# SCH_OpenIDS2.net
KiCad netlist of a schematic drawn in EasyEDA
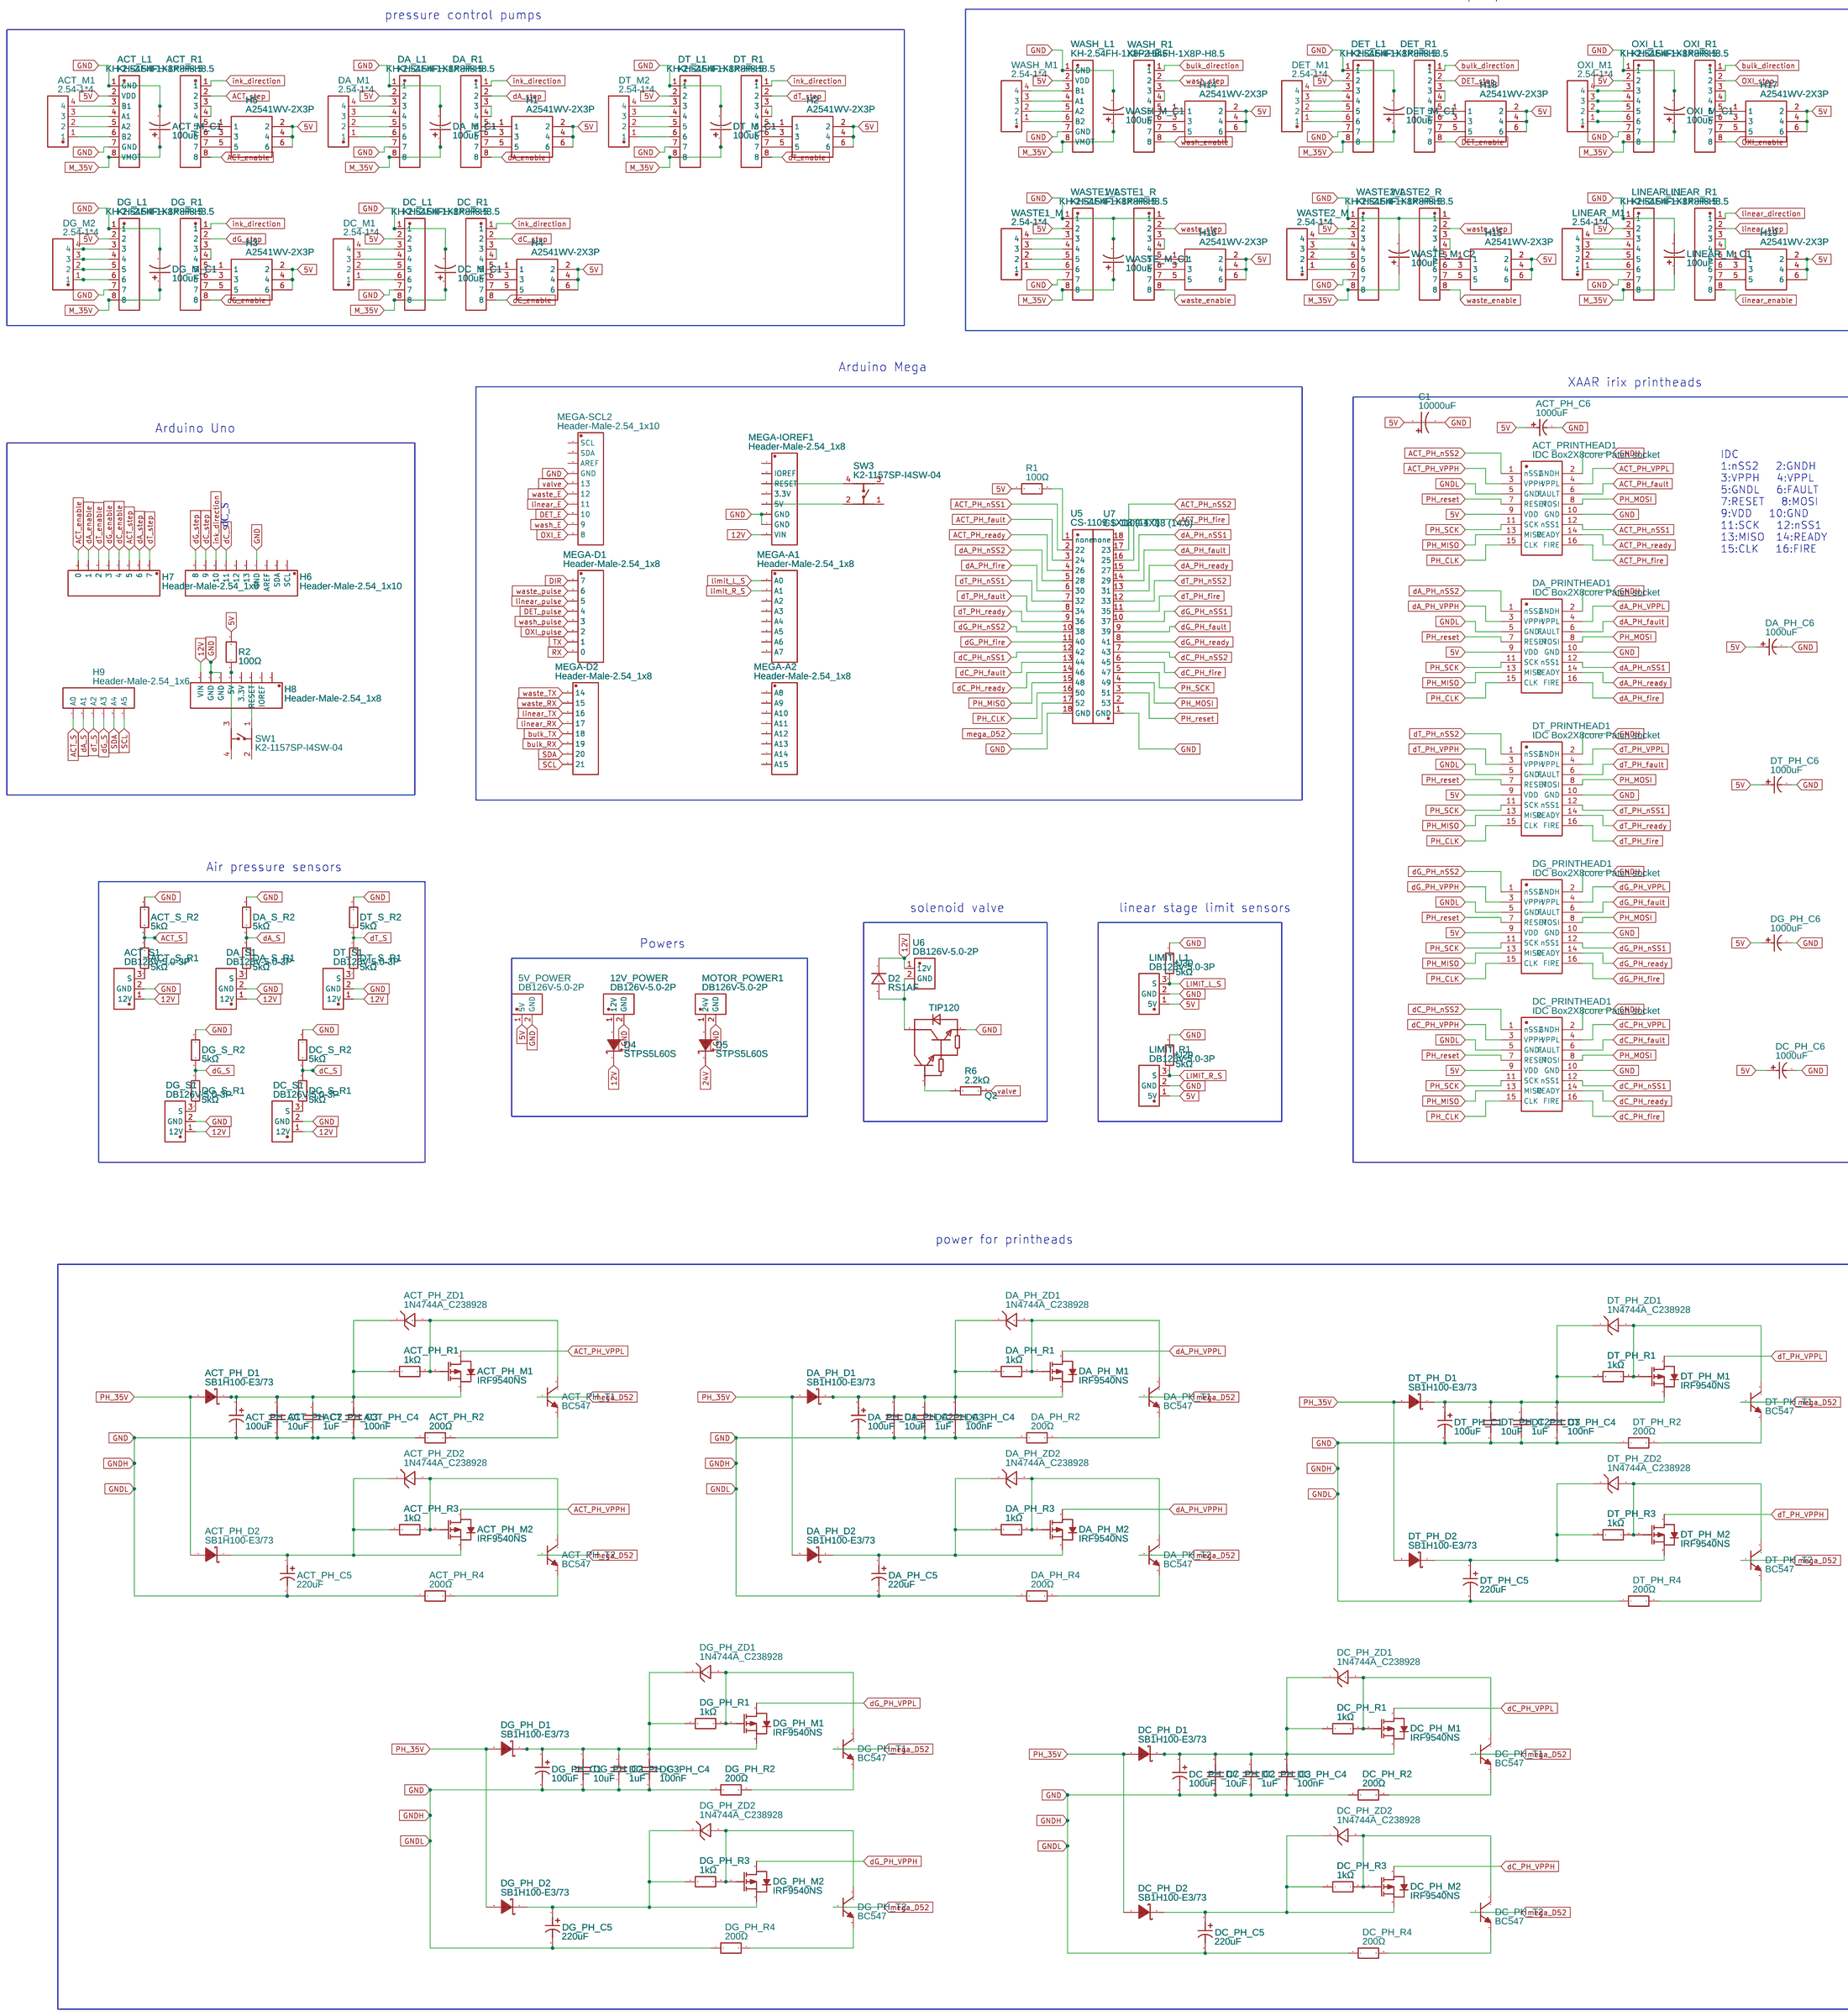
[diagram p0: schematic sheet]

(export (version "E")
  (design (tool "Eeschema 10.0.6"))
  (components
    (comp (ref "5V_POWER")
      (value "DB126V-5.0-2P")
      (fields
        (field (name "Manufacturer Part") "DB126V-5.0-2P-GN-P")
        (field (name "Manufacturer") "DORABO(地博电气)")
      )
      (libsource (lib "") (part "DB126V-5.0-2P_1"))
    )
    (comp (ref "12V_POWER")
      (value "DB126V-5.0-2P")
      (fields
        (field (name "Manufacturer Part") "DB126V-5.0-2P-GN-P")
        (field (name "Manufacturer") "DORABO(地博电气)")
      )
      (libsource (lib "") (part "DB126V-5.0-2P"))
    )
    (comp (ref "ACT_L1")
      (value "KH-2.54FH-1X8P-H8.5")
      (fields (field (name "Manufacturer") "kinghelm(金航标)"))
      (libsource (lib "") (part "KH-2.54FH-1X8P-H8.5_8"))
    )
    (comp (ref "ACT_M1")
      (value "2.54-1*4")
      (fields (field (name "Manufacturer") "ZHOURI(洲日)"))
      (libsource (lib "") (part "2.54-1*4_7"))
    )
    (comp (ref "ACT_M_C1")
      (value "100uF")
      (fields
        (field (name "Manufacturer Part") "50YXF100MEFCCE8X11.5")
        (field (name "Manufacturer") "rubycon(红宝石)")
      )
      (libsource (lib "") (part "50YXF100MEFCCE8X11.5_7"))
    )
    (comp (ref "ACT_PH_C1")
      (value "100uF")
      (fields (field (name "Manufacturer Part") "1011001013R00") (field (name "Manufacturer") "NJCON(永立)"))
      (libsource (lib "") (part "1011001013R00_3"))
    )
    (comp (ref "ACT_PH_C2")
      (value "10uF")
      (fields (field (name "Manufacturer Part") "C1210X106K050T") (field (name "Manufacturer") "IHHEC(禾伸堂)"))
      (libsource (lib "") (part "C1210X106K050T_4"))
    )
    (comp (ref "ACT_PH_C3")
      (value "1uF")
      (fields (field (name "Manufacturer Part") "1210B105K101NT") (field (name "Manufacturer") "FH(风华)"))
      (libsource (lib "") (part "1210B105K101NT_2"))
    )
    (comp (ref "ACT_PH_C4")
      (value "100nF")
      (fields (field (name "Manufacturer Part") "C1005X7R1H104KT000S") (field (name "Manufacturer") "TDK"))
      (libsource (lib "") (part "C1005X7R1H104KT000S"))
    )
    (comp (ref "ACT_PH_C5")
      (value "220uF")
      (fields
        (field (name "Manufacturer Part") "RVT1H221M1010 220UF 50V")
        (field (name "Manufacturer") "DMBJ(振宝佳)")
      )
      (libsource (lib "") (part "RVT1H221M1010 220UF 50V_4"))
    )
    (comp (ref "ACT_PH_C6")
      (value "1000uF")
      (fields (field (name "Manufacturer Part") "KF102M010F140A") (field (name "Manufacturer") "CapXon(丰宾)"))
      (libsource (lib "") (part "KF102M010F140A_4"))
    )
    (comp (ref "ACT_PH_D1")
      (value "SB1H100-E3/73")
      (fields (field (name "Manufacturer") "VISHAY(威世)"))
      (libsource (lib "") (part "SB1H100-E3/73_2"))
    )
    (comp (ref "ACT_PH_D2")
      (value "SB1H100-E3/73")
      (fields (field (name "Manufacturer") "VISHAY(威世)"))
      (libsource (lib "") (part "SB1H100-E3/73_2"))
    )
    (comp (ref "ACT_PH_M1")
      (value "IRF9540NS")
      (fields (field (name "Manufacturer") "minos(迈诺斯)"))
      (libsource (lib "") (part "IRF9540NS"))
    )
    (comp (ref "ACT_PH_M2")
      (value "IRF9540NS")
      (fields (field (name "Manufacturer") "minos(迈诺斯)"))
      (libsource (lib "") (part "IRF9540NS"))
    )
    (comp (ref "ACT_PH_R1")
      (value "1kΩ")
      (fields
        (field (name "Manufacturer Part") "HoCR2512-2W-1KR-5%")
        (field (name "Manufacturer") "Milliohm(毫欧)")
      )
      (libsource (lib "") (part "HOCR2512-2W-1KR-5%_1"))
    )
    (comp (ref "ACT_PH_R2")
      (value "200Ω")
      (fields (field (name "Manufacturer Part") "CR1/4W-200Ω±5%-ST52") (field (name "Manufacturer") "VO(翔胜)"))
      (libsource (lib "") (part "CR1/4W-200Ω±5%-ST52_3"))
    )
    (comp (ref "ACT_PH_R3")
      (value "1kΩ")
      (fields
        (field (name "Manufacturer Part") "HoCR2512-2W-1KR-5%")
        (field (name "Manufacturer") "Milliohm(毫欧)")
      )
      (libsource (lib "") (part "HOCR2512-2W-1KR-5%_1"))
    )
    (comp (ref "ACT_PH_R4")
      (value "200Ω")
      (fields (field (name "Manufacturer Part") "CR1/4W-200Ω±5%-ST52") (field (name "Manufacturer") "VO(翔胜)"))
      (libsource (lib "") (part "CR1/4W-200Ω±5%-ST52_3"))
    )
    (comp (ref "ACT_PH_T1")
      (value "BC547")
      (fields
        (field (name "Manufacturer Part") "BC547(RANGE:420-800)")
        (field (name "Manufacturer") "CJ(江苏长电/长晶)")
      )
      (libsource (lib "") (part "BC547_3"))
    )
    (comp (ref "ACT_PH_T2")
      (value "BC547")
      (fields
        (field (name "Manufacturer Part") "BC547(RANGE:420-800)")
        (field (name "Manufacturer") "CJ(江苏长电/长晶)")
      )
      (libsource (lib "") (part "BC547_3"))
    )
    (comp (ref "ACT_PH_ZD1")
      (value "1N4744A_C238928")
      (fields (field (name "Manufacturer Part") "1N4744A") (field (name "Manufacturer") "onsemi(安森美)"))
      (libsource (lib "") (part "1N4744A_C238928_4"))
    )
    (comp (ref "ACT_PH_ZD2")
      (value "1N4744A_C238928")
      (fields (field (name "Manufacturer Part") "1N4744A") (field (name "Manufacturer") "onsemi(安森美)"))
      (libsource (lib "") (part "1N4744A_C238928_4"))
    )
    (comp (ref "ACT_PRINTHEAD1")
      (value "IDC Box2X8core Patch socket")
      (fields (field (name "Manufacturer Part") "2.0-2*8P立贴简牛") (field (name "Manufacturer") "BOOMELE(博穆精密)"))
      (libsource (lib "") (part "IDC Box2X8core Patch socket_1"))
    )
    (comp (ref "ACT_R1")
      (value "KH-2.54FH-1X8P-H8.5")
      (fields (field (name "Manufacturer") "kinghelm(金航标)"))
      (libsource (lib "") (part "KH-2.54FH-1X8P-H8.5_13"))
    )
    (comp (ref "ACT_S1")
      (value "DB126V-5.0-3P")
      (fields
        (field (name "Manufacturer Part") "DB126V-5.0-3P-GN")
        (field (name "Manufacturer") "DORABO(地博电气)")
      )
      (libsource (lib "") (part "DB126V-5.0-3P_2"))
    )
    (comp (ref "ACT_S_R1")
      (value "5kΩ")
      (fields (field (name "Manufacturer Part") "RT0603BRE075KL") (field (name "Manufacturer") "YAGEO(国巨)"))
      (libsource (lib "") (part "RT0603BRE075KL_2"))
    )
    (comp (ref "ACT_S_R2")
      (value "5kΩ")
      (fields (field (name "Manufacturer Part") "RT0603BRE075KL") (field (name "Manufacturer") "YAGEO(国巨)"))
      (libsource (lib "") (part "RT0603BRE075KL_2"))
    )
    (comp (ref "C1")
      (value "10000uF")
      (fields
        (field (name "Manufacturer Part") "KM1C103ML350A00CV0")
        (field (name "Manufacturer") "HUAWEI(华威集团)")
      )
      (libsource (lib "") (part "KM1C103ML350A00CV0"))
    )
    (comp (ref "D2")
      (value "RS1AF")
      (fields (field (name "Manufacturer") "SHIKUES(时科)"))
      (libsource (lib "") (part "RS1AF"))
    )
    (comp (ref "D4")
      (value "STPS5L60S")
      (fields (field (name "Manufacturer") "ST(意法半导体)"))
      (libsource (lib "") (part "STPS5L60S"))
    )
    (comp (ref "D5")
      (value "STPS5L60S")
      (fields (field (name "Manufacturer") "ST(意法半导体)"))
      (libsource (lib "") (part "STPS5L60S"))
    )
    (comp (ref "DA_L1")
      (value "KH-2.54FH-1X8P-H8.5")
      (fields (field (name "Manufacturer") "kinghelm(金航标)"))
      (libsource (lib "") (part "KH-2.54FH-1X8P-H8.5_14"))
    )
    (comp (ref "DA_M1")
      (value "2.54-1*4")
      (fields (field (name "Manufacturer") "ZHOURI(洲日)"))
      (libsource (lib "") (part "2.54-1*4_4"))
    )
    (comp (ref "DA_M_C1")
      (value "100uF")
      (fields
        (field (name "Manufacturer Part") "50YXF100MEFCCE8X11.5")
        (field (name "Manufacturer") "rubycon(红宝石)")
      )
      (libsource (lib "") (part "50YXF100MEFCCE8X11.5_1"))
    )
    (comp (ref "DA_PH_C1")
      (value "100uF")
      (fields (field (name "Manufacturer Part") "1011001013R00") (field (name "Manufacturer") "NJCON(永立)"))
      (libsource (lib "") (part "1011001013R00"))
    )
    (comp (ref "DA_PH_C2")
      (value "10uF")
      (fields (field (name "Manufacturer Part") "C1210X106K050T") (field (name "Manufacturer") "IHHEC(禾伸堂)"))
      (libsource (lib "") (part "C1210X106K050T_1"))
    )
    (comp (ref "DA_PH_C3")
      (value "1uF")
      (fields (field (name "Manufacturer Part") "1210B105K101NT") (field (name "Manufacturer") "FH(风华)"))
      (libsource (lib "") (part "1210B105K101NT_4"))
    )
    (comp (ref "DA_PH_C4")
      (value "100nF")
      (fields (field (name "Manufacturer Part") "C1005X7R1H104KT000S") (field (name "Manufacturer") "TDK"))
      (libsource (lib "") (part "C1005X7R1H104KT000S_2"))
    )
    (comp (ref "DA_PH_C5")
      (value "220uF")
      (fields
        (field (name "Manufacturer Part") "RVT1H221M1010 220UF 50V")
        (field (name "Manufacturer") "DMBJ(振宝佳)")
      )
      (libsource (lib "") (part "RVT1H221M1010 220UF 50V"))
    )
    (comp (ref "DA_PH_C6")
      (value "1000uF")
      (fields (field (name "Manufacturer Part") "KF102M010F140A") (field (name "Manufacturer") "CapXon(丰宾)"))
      (libsource (lib "") (part "KF102M010F140A_1"))
    )
    (comp (ref "DA_PH_D1")
      (value "SB1H100-E3/73")
      (fields (field (name "Manufacturer") "VISHAY(威世)"))
      (libsource (lib "") (part "SB1H100-E3/73_3"))
    )
    (comp (ref "DA_PH_D2")
      (value "SB1H100-E3/73")
      (fields (field (name "Manufacturer") "VISHAY(威世)"))
      (libsource (lib "") (part "SB1H100-E3/73_3"))
    )
    (comp (ref "DA_PH_M1")
      (value "IRF9540NS")
      (fields (field (name "Manufacturer") "minos(迈诺斯)"))
      (libsource (lib "") (part "IRF9540NS_1"))
    )
    (comp (ref "DA_PH_M2")
      (value "IRF9540NS")
      (fields (field (name "Manufacturer") "minos(迈诺斯)"))
      (libsource (lib "") (part "IRF9540NS_1"))
    )
    (comp (ref "DA_PH_R1")
      (value "1kΩ")
      (fields
        (field (name "Manufacturer Part") "HoCR2512-2W-1KR-5%")
        (field (name "Manufacturer") "Milliohm(毫欧)")
      )
      (libsource (lib "") (part "HOCR2512-2W-1KR-5%_2"))
    )
    (comp (ref "DA_PH_R2")
      (value "200Ω")
      (fields (field (name "Manufacturer Part") "CR1/4W-200Ω±5%-ST52") (field (name "Manufacturer") "VO(翔胜)"))
      (libsource (lib "") (part "CR1/4W-200Ω±5%-ST52_2"))
    )
    (comp (ref "DA_PH_R3")
      (value "1kΩ")
      (fields
        (field (name "Manufacturer Part") "HoCR2512-2W-1KR-5%")
        (field (name "Manufacturer") "Milliohm(毫欧)")
      )
      (libsource (lib "") (part "HOCR2512-2W-1KR-5%_2"))
    )
    (comp (ref "DA_PH_R4")
      (value "200Ω")
      (fields (field (name "Manufacturer Part") "CR1/4W-200Ω±5%-ST52") (field (name "Manufacturer") "VO(翔胜)"))
      (libsource (lib "") (part "CR1/4W-200Ω±5%-ST52_2"))
    )
    (comp (ref "DA_PH_T1")
      (value "BC547")
      (fields
        (field (name "Manufacturer Part") "BC547(RANGE:420-800)")
        (field (name "Manufacturer") "CJ(江苏长电/长晶)")
      )
      (libsource (lib "") (part "BC547_2"))
    )
    (comp (ref "DA_PH_T2")
      (value "BC547")
      (fields
        (field (name "Manufacturer Part") "BC547(RANGE:420-800)")
        (field (name "Manufacturer") "CJ(江苏长电/长晶)")
      )
      (libsource (lib "") (part "BC547_2"))
    )
    (comp (ref "DA_PH_ZD1")
      (value "1N4744A_C238928")
      (fields (field (name "Manufacturer Part") "1N4744A") (field (name "Manufacturer") "onsemi(安森美)"))
      (libsource (lib "") (part "1N4744A_C238928_3"))
    )
    (comp (ref "DA_PH_ZD2")
      (value "1N4744A_C238928")
      (fields (field (name "Manufacturer Part") "1N4744A") (field (name "Manufacturer") "onsemi(安森美)"))
      (libsource (lib "") (part "1N4744A_C238928_3"))
    )
    (comp (ref "DA_PRINTHEAD1")
      (value "IDC Box2X8core Patch socket")
      (fields (field (name "Manufacturer Part") "2.0-2*8P立贴简牛") (field (name "Manufacturer") "BOOMELE(博穆精密)"))
      (libsource (lib "") (part "IDC Box2X8core Patch socket_4"))
    )
    (comp (ref "DA_R1")
      (value "KH-2.54FH-1X8P-H8.5")
      (fields (field (name "Manufacturer") "kinghelm(金航标)"))
      (libsource (lib "") (part "KH-2.54FH-1X8P-H8.5_3"))
    )
    (comp (ref "DA_S1")
      (value "DB126V-5.0-3P")
      (fields
        (field (name "Manufacturer Part") "DB126V-5.0-3P-GN")
        (field (name "Manufacturer") "DORABO(地博电气)")
      )
      (libsource (lib "") (part "DB126V-5.0-3P_3"))
    )
    (comp (ref "DA_S_R1")
      (value "5kΩ")
      (fields (field (name "Manufacturer Part") "RT0603BRE075KL") (field (name "Manufacturer") "YAGEO(国巨)"))
      (libsource (lib "") (part "RT0603BRE075KL"))
    )
    (comp (ref "DA_S_R2")
      (value "5kΩ")
      (fields (field (name "Manufacturer Part") "RT0603BRE075KL") (field (name "Manufacturer") "YAGEO(国巨)"))
      (libsource (lib "") (part "RT0603BRE075KL"))
    )
    (comp (ref "DC_L1")
      (value "KH-2.54FH-1X8P-H8.5")
      (fields (field (name "Manufacturer") "kinghelm(金航标)"))
      (libsource (lib "") (part "KH-2.54FH-1X8P-H8.5_19"))
    )
    (comp (ref "DC_M1")
      (value "2.54-1*4")
      (fields (field (name "Manufacturer") "ZHOURI(洲日)"))
      (libsource (lib "") (part "2.54-1*4_6"))
    )
    (comp (ref "DC_M_C1")
      (value "100uF")
      (fields
        (field (name "Manufacturer Part") "50YXF100MEFCCE8X11.5")
        (field (name "Manufacturer") "rubycon(红宝石)")
      )
      (libsource (lib "") (part "50YXF100MEFCCE8X11.5"))
    )
    (comp (ref "DC_PH_C2")
      (value "10uF")
      (fields (field (name "Manufacturer Part") "C1210X106K050T") (field (name "Manufacturer") "IHHEC(禾伸堂)"))
      (libsource (lib "") (part "C1210X106K050T_2"))
    )
    (comp (ref "DC_PH_C3")
      (value "1uF")
      (fields (field (name "Manufacturer Part") "1210B105K101NT") (field (name "Manufacturer") "FH(风华)"))
      (libsource (lib "") (part "1210B105K101NT_3"))
    )
    (comp (ref "DC_PH_C4")
      (value "100nF")
      (fields (field (name "Manufacturer Part") "C1005X7R1H104KT000S") (field (name "Manufacturer") "TDK"))
      (libsource (lib "") (part "C1005X7R1H104KT000S_3"))
    )
    (comp (ref "DC_PH_C5")
      (value "220uF")
      (fields
        (field (name "Manufacturer Part") "RVT1H221M1010 220UF 50V")
        (field (name "Manufacturer") "DMBJ(振宝佳)")
      )
      (libsource (lib "") (part "RVT1H221M1010 220UF 50V_3"))
    )
    (comp (ref "DC_PH_C6")
      (value "1000uF")
      (fields (field (name "Manufacturer Part") "KF102M010F140A") (field (name "Manufacturer") "CapXon(丰宾)"))
      (libsource (lib "") (part "KF102M010F140A_2"))
    )
    (comp (ref "DC_PH_C7")
      (value "100uF")
      (fields (field (name "Manufacturer Part") "1011001013R00") (field (name "Manufacturer") "NJCON(永立)"))
      (libsource (lib "") (part "1011001013R00_2"))
    )
    (comp (ref "DC_PH_D1")
      (value "SB1H100-E3/73")
      (fields (field (name "Manufacturer") "VISHAY(威世)"))
      (libsource (lib "") (part "SB1H100-E3/73_4"))
    )
    (comp (ref "DC_PH_D2")
      (value "SB1H100-E3/73")
      (fields (field (name "Manufacturer") "VISHAY(威世)"))
      (libsource (lib "") (part "SB1H100-E3/73_4"))
    )
    (comp (ref "DC_PH_M1")
      (value "IRF9540NS")
      (fields (field (name "Manufacturer") "minos(迈诺斯)"))
      (libsource (lib "") (part "IRF9540NS_4"))
    )
    (comp (ref "DC_PH_M2")
      (value "IRF9540NS")
      (fields (field (name "Manufacturer") "minos(迈诺斯)"))
      (libsource (lib "") (part "IRF9540NS_4"))
    )
    (comp (ref "DC_PH_R1")
      (value "1kΩ")
      (fields
        (field (name "Manufacturer Part") "HoCR2512-2W-1KR-5%")
        (field (name "Manufacturer") "Milliohm(毫欧)")
      )
      (libsource (lib "") (part "HOCR2512-2W-1KR-5%"))
    )
    (comp (ref "DC_PH_R2")
      (value "200Ω")
      (fields (field (name "Manufacturer Part") "CR1/4W-200Ω±5%-ST52") (field (name "Manufacturer") "VO(翔胜)"))
      (libsource (lib "") (part "CR1/4W-200Ω±5%-ST52_4"))
    )
    (comp (ref "DC_PH_R3")
      (value "1kΩ")
      (fields
        (field (name "Manufacturer Part") "HoCR2512-2W-1KR-5%")
        (field (name "Manufacturer") "Milliohm(毫欧)")
      )
      (libsource (lib "") (part "HOCR2512-2W-1KR-5%"))
    )
    (comp (ref "DC_PH_R4")
      (value "200Ω")
      (fields (field (name "Manufacturer Part") "CR1/4W-200Ω±5%-ST52") (field (name "Manufacturer") "VO(翔胜)"))
      (libsource (lib "") (part "CR1/4W-200Ω±5%-ST52_4"))
    )
    (comp (ref "DC_PH_T1")
      (value "BC547")
      (fields
        (field (name "Manufacturer Part") "BC547(RANGE:420-800)")
        (field (name "Manufacturer") "CJ(江苏长电/长晶)")
      )
      (libsource (lib "") (part "BC547_4"))
    )
    (comp (ref "DC_PH_T2")
      (value "BC547")
      (fields
        (field (name "Manufacturer Part") "BC547(RANGE:420-800)")
        (field (name "Manufacturer") "CJ(江苏长电/长晶)")
      )
      (libsource (lib "") (part "BC547_4"))
    )
    (comp (ref "DC_PH_ZD1")
      (value "1N4744A_C238928")
      (fields (field (name "Manufacturer Part") "1N4744A") (field (name "Manufacturer") "onsemi(安森美)"))
      (libsource (lib "") (part "1N4744A_C238928"))
    )
    (comp (ref "DC_PH_ZD2")
      (value "1N4744A_C238928")
      (fields (field (name "Manufacturer Part") "1N4744A") (field (name "Manufacturer") "onsemi(安森美)"))
      (libsource (lib "") (part "1N4744A_C238928"))
    )
    (comp (ref "DC_PRINTHEAD1")
      (value "IDC Box2X8core Patch socket")
      (fields (field (name "Manufacturer Part") "2.0-2*8P立贴简牛") (field (name "Manufacturer") "BOOMELE(博穆精密)"))
      (libsource (lib "") (part "IDC Box2X8core Patch socket_2"))
    )
    (comp (ref "DC_R1")
      (value "KH-2.54FH-1X8P-H8.5")
      (fields (field (name "Manufacturer") "kinghelm(金航标)"))
      (libsource (lib "") (part "KH-2.54FH-1X8P-H8.5_15"))
    )
    (comp (ref "DC_S1")
      (value "DB126V-5.0-3P")
      (fields
        (field (name "Manufacturer Part") "DB126V-5.0-3P-GN")
        (field (name "Manufacturer") "DORABO(地博电气)")
      )
      (libsource (lib "") (part "DB126V-5.0-3P_4"))
    )
    (comp (ref "DC_S_R1")
      (value "5kΩ")
      (fields (field (name "Manufacturer Part") "RT0603BRE075KL") (field (name "Manufacturer") "YAGEO(国巨)"))
      (libsource (lib "") (part "RT0603BRE075KL_3"))
    )
    (comp (ref "DC_S_R2")
      (value "5kΩ")
      (fields (field (name "Manufacturer Part") "RT0603BRE075KL") (field (name "Manufacturer") "YAGEO(国巨)"))
      (libsource (lib "") (part "RT0603BRE075KL_3"))
    )
    (comp (ref "DET_L1")
      (value "KH-2.54FH-1X8P-H8.5")
      (fields (field (name "Manufacturer") "kinghelm(金航标)"))
      (libsource (lib "") (part "KH-2.54FH-1X8P-H8.5_21"))
    )
    (comp (ref "DET_M1")
      (value "2.54-1*4")
      (fields (field (name "Manufacturer") "ZHOURI(洲日)"))
      (libsource (lib "") (part "2.54-1*4_3"))
    )
    (comp (ref "DET_M_C1")
      (value "100uF")
      (fields
        (field (name "Manufacturer Part") "50YXF100MEFCCE8X11.5")
        (field (name "Manufacturer") "rubycon(红宝石)")
      )
      (libsource (lib "") (part "50YXF100MEFCCE8X11.5_4"))
    )
    (comp (ref "DET_R1")
      (value "KH-2.54FH-1X8P-H8.5")
      (fields (field (name "Manufacturer") "kinghelm(金航标)"))
      (libsource (lib "") (part "KH-2.54FH-1X8P-H8.5_10"))
    )
    (comp (ref "DG_L1")
      (value "KH-2.54FH-1X8P-H8.5")
      (fields (field (name "Manufacturer") "kinghelm(金航标)"))
      (libsource (lib "") (part "KH-2.54FH-1X8P-H8.5_1"))
    )
    (comp (ref "DG_M2")
      (value "2.54-1*4")
      (fields (field (name "Manufacturer") "ZHOURI(洲日)"))
      (libsource (lib "") (part "2.54-1*4"))
    )
    (comp (ref "DG_M_C1")
      (value "100uF")
      (fields
        (field (name "Manufacturer Part") "50YXF100MEFCCE8X11.5")
        (field (name "Manufacturer") "rubycon(红宝石)")
      )
      (libsource (lib "") (part "50YXF100MEFCCE8X11.5_3"))
    )
    (comp (ref "DG_PH_C1")
      (value "100uF")
      (fields (field (name "Manufacturer Part") "1011001013R00") (field (name "Manufacturer") "NJCON(永立)"))
      (libsource (lib "") (part "1011001013R00_4"))
    )
    (comp (ref "DG_PH_C2")
      (value "10uF")
      (fields (field (name "Manufacturer Part") "C1210X106K050T") (field (name "Manufacturer") "IHHEC(禾伸堂)"))
      (libsource (lib "") (part "C1210X106K050T"))
    )
    (comp (ref "DG_PH_C3")
      (value "1uF")
      (fields (field (name "Manufacturer Part") "1210B105K101NT") (field (name "Manufacturer") "FH(风华)"))
      (libsource (lib "") (part "1210B105K101NT_1"))
    )
    (comp (ref "DG_PH_C4")
      (value "100nF")
      (fields (field (name "Manufacturer Part") "C1005X7R1H104KT000S") (field (name "Manufacturer") "TDK"))
      (libsource (lib "") (part "C1005X7R1H104KT000S_4"))
    )
    (comp (ref "DG_PH_C5")
      (value "220uF")
      (fields
        (field (name "Manufacturer Part") "RVT1H221M1010 220UF 50V")
        (field (name "Manufacturer") "DMBJ(振宝佳)")
      )
      (libsource (lib "") (part "RVT1H221M1010 220UF 50V_1"))
    )
    (comp (ref "DG_PH_C6")
      (value "1000uF")
      (fields (field (name "Manufacturer Part") "KF102M010F140A") (field (name "Manufacturer") "CapXon(丰宾)"))
      (libsource (lib "") (part "KF102M010F140A_3"))
    )
    (comp (ref "DG_PH_D1")
      (value "SB1H100-E3/73")
      (fields (field (name "Manufacturer") "VISHAY(威世)"))
      (libsource (lib "") (part "SB1H100-E3/73_1"))
    )
    (comp (ref "DG_PH_D2")
      (value "SB1H100-E3/73")
      (fields (field (name "Manufacturer") "VISHAY(威世)"))
      (libsource (lib "") (part "SB1H100-E3/73_1"))
    )
    (comp (ref "DG_PH_M1")
      (value "IRF9540NS")
      (fields (field (name "Manufacturer") "minos(迈诺斯)"))
      (libsource (lib "") (part "IRF9540NS_2"))
    )
    (comp (ref "DG_PH_M2")
      (value "IRF9540NS")
      (fields (field (name "Manufacturer") "minos(迈诺斯)"))
      (libsource (lib "") (part "IRF9540NS_2"))
    )
    (comp (ref "DG_PH_R1")
      (value "1kΩ")
      (fields
        (field (name "Manufacturer Part") "HoCR2512-2W-1KR-5%")
        (field (name "Manufacturer") "Milliohm(毫欧)")
      )
      (libsource (lib "") (part "HOCR2512-2W-1KR-5%_3"))
    )
    (comp (ref "DG_PH_R2")
      (value "200Ω")
      (fields (field (name "Manufacturer Part") "CR1/4W-200Ω±5%-ST52") (field (name "Manufacturer") "VO(翔胜)"))
      (libsource (lib "") (part "CR1/4W-200Ω±5%-ST52"))
    )
    (comp (ref "DG_PH_R3")
      (value "1kΩ")
      (fields
        (field (name "Manufacturer Part") "HoCR2512-2W-1KR-5%")
        (field (name "Manufacturer") "Milliohm(毫欧)")
      )
      (libsource (lib "") (part "HOCR2512-2W-1KR-5%_3"))
    )
    (comp (ref "DG_PH_R4")
      (value "200Ω")
      (fields (field (name "Manufacturer Part") "CR1/4W-200Ω±5%-ST52") (field (name "Manufacturer") "VO(翔胜)"))
      (libsource (lib "") (part "CR1/4W-200Ω±5%-ST52"))
    )
    (comp (ref "DG_PH_T1")
      (value "BC547")
      (fields
        (field (name "Manufacturer Part") "BC547(RANGE:420-800)")
        (field (name "Manufacturer") "CJ(江苏长电/长晶)")
      )
      (libsource (lib "") (part "BC547"))
    )
    (comp (ref "DG_PH_T2")
      (value "BC547")
      (fields
        (field (name "Manufacturer Part") "BC547(RANGE:420-800)")
        (field (name "Manufacturer") "CJ(江苏长电/长晶)")
      )
      (libsource (lib "") (part "BC547"))
    )
    (comp (ref "DG_PH_ZD1")
      (value "1N4744A_C238928")
      (fields (field (name "Manufacturer Part") "1N4744A") (field (name "Manufacturer") "onsemi(安森美)"))
      (libsource (lib "") (part "1N4744A_C238928_2"))
    )
    (comp (ref "DG_PH_ZD2")
      (value "1N4744A_C238928")
      (fields (field (name "Manufacturer Part") "1N4744A") (field (name "Manufacturer") "onsemi(安森美)"))
      (libsource (lib "") (part "1N4744A_C238928_2"))
    )
    (comp (ref "DG_PRINTHEAD1")
      (value "IDC Box2X8core Patch socket")
      (fields (field (name "Manufacturer Part") "2.0-2*8P立贴简牛") (field (name "Manufacturer") "BOOMELE(博穆精密)"))
      (libsource (lib "") (part "IDC Box2X8core Patch socket_3"))
    )
    (comp (ref "DG_R1")
      (value "KH-2.54FH-1X8P-H8.5")
      (fields (field (name "Manufacturer") "kinghelm(金航标)"))
      (libsource (lib "") (part "KH-2.54FH-1X8P-H8.5_9"))
    )
    (comp (ref "DG_S1")
      (value "DB126V-5.0-3P")
      (fields
        (field (name "Manufacturer Part") "DB126V-5.0-3P-GN")
        (field (name "Manufacturer") "DORABO(地博电气)")
      )
      (libsource (lib "") (part "DB126V-5.0-3P_1"))
    )
    (comp (ref "DG_S_R1")
      (value "5kΩ")
      (fields (field (name "Manufacturer Part") "RT0603BRE075KL") (field (name "Manufacturer") "YAGEO(国巨)"))
      (libsource (lib "") (part "RT0603BRE075KL_4"))
    )
    (comp (ref "DG_S_R2")
      (value "5kΩ")
      (fields (field (name "Manufacturer Part") "RT0603BRE075KL") (field (name "Manufacturer") "YAGEO(国巨)"))
      (libsource (lib "") (part "RT0603BRE075KL_4"))
    )
    (comp (ref "DT_L1")
      (value "KH-2.54FH-1X8P-H8.5")
      (fields (field (name "Manufacturer") "kinghelm(金航标)"))
      (libsource (lib "") (part "KH-2.54FH-1X8P-H8.5_4"))
    )
    (comp (ref "DT_M2")
      (value "2.54-1*4")
      (fields (field (name "Manufacturer") "ZHOURI(洲日)"))
      (libsource (lib "") (part "2.54-1*4_5"))
    )
    (comp (ref "DT_M_C1")
      (value "100uF")
      (fields
        (field (name "Manufacturer Part") "50YXF100MEFCCE8X11.5")
        (field (name "Manufacturer") "rubycon(红宝石)")
      )
      (libsource (lib "") (part "50YXF100MEFCCE8X11.5_9"))
    )
    (comp (ref "DT_PH_C1")
      (value "100uF")
      (fields (field (name "Manufacturer Part") "1011001013R00") (field (name "Manufacturer") "NJCON(永立)"))
      (libsource (lib "") (part "1011001013R00_1"))
    )
    (comp (ref "DT_PH_C2")
      (value "10uF")
      (fields (field (name "Manufacturer Part") "C1210X106K050T") (field (name "Manufacturer") "IHHEC(禾伸堂)"))
      (libsource (lib "") (part "C1210X106K050T_3"))
    )
    (comp (ref "DT_PH_C3")
      (value "1uF")
      (fields (field (name "Manufacturer Part") "1210B105K101NT") (field (name "Manufacturer") "FH(风华)"))
      (libsource (lib "") (part "1210B105K101NT"))
    )
    (comp (ref "DT_PH_C4")
      (value "100nF")
      (fields (field (name "Manufacturer Part") "C1005X7R1H104KT000S") (field (name "Manufacturer") "TDK"))
      (libsource (lib "") (part "C1005X7R1H104KT000S_1"))
    )
    (comp (ref "DT_PH_C5")
      (value "220uF")
      (fields
        (field (name "Manufacturer Part") "RVT1H221M1010 220UF 50V")
        (field (name "Manufacturer") "DMBJ(振宝佳)")
      )
      (libsource (lib "") (part "RVT1H221M1010 220UF 50V_2"))
    )
    (comp (ref "DT_PH_C6")
      (value "1000uF")
      (fields (field (name "Manufacturer Part") "KF102M010F140A") (field (name "Manufacturer") "CapXon(丰宾)"))
      (libsource (lib "") (part "KF102M010F140A"))
    )
    (comp (ref "DT_PH_D1")
      (value "SB1H100-E3/73")
      (fields (field (name "Manufacturer") "VISHAY(威世)"))
      (libsource (lib "") (part "SB1H100-E3/73"))
    )
    (comp (ref "DT_PH_D2")
      (value "SB1H100-E3/73")
      (fields (field (name "Manufacturer") "VISHAY(威世)"))
      (libsource (lib "") (part "SB1H100-E3/73"))
    )
    (comp (ref "DT_PH_M1")
      (value "IRF9540NS")
      (fields (field (name "Manufacturer") "minos(迈诺斯)"))
      (libsource (lib "") (part "IRF9540NS_3"))
    )
    (comp (ref "DT_PH_M2")
      (value "IRF9540NS")
      (fields (field (name "Manufacturer") "minos(迈诺斯)"))
      (libsource (lib "") (part "IRF9540NS_3"))
    )
    (comp (ref "DT_PH_R1")
      (value "1kΩ")
      (fields
        (field (name "Manufacturer Part") "HoCR2512-2W-1KR-5%")
        (field (name "Manufacturer") "Milliohm(毫欧)")
      )
      (libsource (lib "") (part "HOCR2512-2W-1KR-5%_4"))
    )
    (comp (ref "DT_PH_R2")
      (value "200Ω")
      (fields (field (name "Manufacturer Part") "CR1/4W-200Ω±5%-ST52") (field (name "Manufacturer") "VO(翔胜)"))
      (libsource (lib "") (part "CR1/4W-200Ω±5%-ST52_1"))
    )
    (comp (ref "DT_PH_R3")
      (value "1kΩ")
      (fields
        (field (name "Manufacturer Part") "HoCR2512-2W-1KR-5%")
        (field (name "Manufacturer") "Milliohm(毫欧)")
      )
      (libsource (lib "") (part "HOCR2512-2W-1KR-5%_4"))
    )
    (comp (ref "DT_PH_R4")
      (value "200Ω")
      (fields (field (name "Manufacturer Part") "CR1/4W-200Ω±5%-ST52") (field (name "Manufacturer") "VO(翔胜)"))
      (libsource (lib "") (part "CR1/4W-200Ω±5%-ST52_1"))
    )
    (comp (ref "DT_PH_T1")
      (value "BC547")
      (fields
        (field (name "Manufacturer Part") "BC547(RANGE:420-800)")
        (field (name "Manufacturer") "CJ(江苏长电/长晶)")
      )
      (libsource (lib "") (part "BC547_1"))
    )
    (comp (ref "DT_PH_T2")
      (value "BC547")
      (fields
        (field (name "Manufacturer Part") "BC547(RANGE:420-800)")
        (field (name "Manufacturer") "CJ(江苏长电/长晶)")
      )
      (libsource (lib "") (part "BC547_1"))
    )
    (comp (ref "DT_PH_ZD1")
      (value "1N4744A_C238928")
      (fields (field (name "Manufacturer Part") "1N4744A") (field (name "Manufacturer") "onsemi(安森美)"))
      (libsource (lib "") (part "1N4744A_C238928_1"))
    )
    (comp (ref "DT_PH_ZD2")
      (value "1N4744A_C238928")
      (fields (field (name "Manufacturer Part") "1N4744A") (field (name "Manufacturer") "onsemi(安森美)"))
      (libsource (lib "") (part "1N4744A_C238928_1"))
    )
    (comp (ref "DT_PRINTHEAD1")
      (value "IDC Box2X8core Patch socket")
      (fields (field (name "Manufacturer Part") "2.0-2*8P立贴简牛") (field (name "Manufacturer") "BOOMELE(博穆精密)"))
      (libsource (lib "") (part "IDC Box2X8core Patch socket"))
    )
    (comp (ref "DT_R1")
      (value "KH-2.54FH-1X8P-H8.5")
      (fields (field (name "Manufacturer") "kinghelm(金航标)"))
      (libsource (lib "") (part "KH-2.54FH-1X8P-H8.5_5"))
    )
    (comp (ref "DT_S1")
      (value "DB126V-5.0-3P")
      (fields
        (field (name "Manufacturer Part") "DB126V-5.0-3P-GN")
        (field (name "Manufacturer") "DORABO(地博电气)")
      )
      (libsource (lib "") (part "DB126V-5.0-3P_6"))
    )
    (comp (ref "DT_S_R1")
      (value "5kΩ")
      (fields (field (name "Manufacturer Part") "RT0603BRE075KL") (field (name "Manufacturer") "YAGEO(国巨)"))
      (libsource (lib "") (part "RT0603BRE075KL_1"))
    )
    (comp (ref "DT_S_R2")
      (value "5kΩ")
      (fields (field (name "Manufacturer Part") "RT0603BRE075KL") (field (name "Manufacturer") "YAGEO(国巨)"))
      (libsource (lib "") (part "RT0603BRE075KL_1"))
    )
    (comp (ref "H1")
      (value "A2541WV-2X3P")
      (fields (field (name "Manufacturer Part") "A2541WV-2x3P") (field (name "Manufacturer") "CJT(长江连接器)"))
      (libsource (lib "") (part "A2541WV-2X3P"))
    )
    (comp (ref "H2")
      (value "A2541WV-2X3P")
      (fields (field (name "Manufacturer Part") "A2541WV-2x3P") (field (name "Manufacturer") "CJT(长江连接器)"))
      (libsource (lib "") (part "A2541WV-2X3P"))
    )
    (comp (ref "H3")
      (value "A2541WV-2X3P")
      (fields (field (name "Manufacturer Part") "A2541WV-2x3P") (field (name "Manufacturer") "CJT(长江连接器)"))
      (libsource (lib "") (part "A2541WV-2X3P"))
    )
    (comp (ref "H4")
      (value "A2541WV-2X3P")
      (fields (field (name "Manufacturer Part") "A2541WV-2x3P") (field (name "Manufacturer") "CJT(长江连接器)"))
      (libsource (lib "") (part "A2541WV-2X3P"))
    )
    (comp (ref "H5")
      (value "A2541WV-2X3P")
      (fields (field (name "Manufacturer Part") "A2541WV-2x3P") (field (name "Manufacturer") "CJT(长江连接器)"))
      (libsource (lib "") (part "A2541WV-2X3P"))
    )
    (comp (ref "H6")
      (value "Header-Male-2.54_1x10")
      (fields (field (name "Manufacturer Part") "2.54-1*10P针") (field (name "Manufacturer") "BOOMELE(博穆精密)"))
      (libsource (lib "") (part "Header-Male-2.54_1x10_1"))
    )
    (comp (ref "H7")
      (value "Header-Male-2.54_1x8")
      (fields (field (name "Manufacturer Part") "B-2100S08P-A110") (field (name "Manufacturer") "Ckmtw(灿科盟)"))
      (libsource (lib "") (part "Header-Male-2.54_1x8_5"))
    )
    (comp (ref "H8")
      (value "Header-Male-2.54_1x8")
      (fields (field (name "Manufacturer Part") "B-2100S08P-A110") (field (name "Manufacturer") "Ckmtw(灿科盟)"))
      (libsource (lib "") (part "Header-Male-2.54_1x8_6"))
    )
    (comp (ref "H9")
      (value "Header-Male-2.54_1x6")
      (fields (field (name "Manufacturer Part") "2.54-1x6P直针") (field (name "Manufacturer") "BOOMELE(博穆精密)"))
      (libsource (lib "") (part "Header-Male-2.54_1x6"))
    )
    (comp (ref "H14")
      (value "A2541WV-2X3P")
      (fields (field (name "Manufacturer Part") "A2541WV-2x3P") (field (name "Manufacturer") "CJT(长江连接器)"))
      (libsource (lib "") (part "A2541WV-2X3P"))
    )
    (comp (ref "H15")
      (value "A2541WV-2X3P")
      (fields (field (name "Manufacturer Part") "A2541WV-2x3P") (field (name "Manufacturer") "CJT(长江连接器)"))
      (libsource (lib "") (part "A2541WV-2X3P"))
    )
    (comp (ref "H16")
      (value "A2541WV-2X3P")
      (fields (field (name "Manufacturer Part") "A2541WV-2x3P") (field (name "Manufacturer") "CJT(长江连接器)"))
      (libsource (lib "") (part "A2541WV-2X3P"))
    )
    (comp (ref "H17")
      (value "A2541WV-2X3P")
      (fields (field (name "Manufacturer Part") "A2541WV-2x3P") (field (name "Manufacturer") "CJT(长江连接器)"))
      (libsource (lib "") (part "A2541WV-2X3P"))
    )
    (comp (ref "H18")
      (value "A2541WV-2X3P")
      (fields (field (name "Manufacturer Part") "A2541WV-2x3P") (field (name "Manufacturer") "CJT(长江连接器)"))
      (libsource (lib "") (part "A2541WV-2X3P"))
    )
    (comp (ref "H19")
      (value "A2541WV-2X3P")
      (fields (field (name "Manufacturer Part") "A2541WV-2x3P") (field (name "Manufacturer") "CJT(长江连接器)"))
      (libsource (lib "") (part "A2541WV-2X3P"))
    )
    (comp (ref "LIMIT_L1")
      (value "DB126V-5.0-3P")
      (fields
        (field (name "Manufacturer Part") "DB126V-5.0-3P-GN")
        (field (name "Manufacturer") "DORABO(地博电气)")
      )
      (libsource (lib "") (part "DB126V-5.0-3P_5"))
    )
    (comp (ref "LIMIT_R1")
      (value "DB126V-5.0-3P")
      (fields
        (field (name "Manufacturer Part") "DB126V-5.0-3P-GN")
        (field (name "Manufacturer") "DORABO(地博电气)")
      )
      (libsource (lib "") (part "DB126V-5.0-3P"))
    )
    (comp (ref "LINEAR_L1")
      (value "KH-2.54FH-1X8P-H8.5")
      (fields (field (name "Manufacturer") "kinghelm(金航标)"))
      (libsource (lib "") (part "KH-2.54FH-1X8P-H8.5_7"))
    )
    (comp (ref "LINEAR_M1")
      (value "2.54-1*4")
      (fields (field (name "Manufacturer") "ZHOURI(洲日)"))
      (libsource (lib "") (part "2.54-1*4_8"))
    )
    (comp (ref "LINEAR_M_C1")
      (value "100uF")
      (fields
        (field (name "Manufacturer Part") "50YXF100MEFCCE8X11.5")
        (field (name "Manufacturer") "rubycon(红宝石)")
      )
      (libsource (lib "") (part "50YXF100MEFCCE8X11.5_5"))
    )
    (comp (ref "LINEAR_R1")
      (value "KH-2.54FH-1X8P-H8.5")
      (fields (field (name "Manufacturer") "kinghelm(金航标)"))
      (libsource (lib "") (part "KH-2.54FH-1X8P-H8.5_16"))
    )
    (comp (ref "MEGA-A1")
      (value "Header-Male-2.54_1x8")
      (fields (field (name "Manufacturer Part") "B-2100S08P-A110") (field (name "Manufacturer") "Ckmtw(灿科盟)"))
      (libsource (lib "") (part "Header-Male-2.54_1x8_3"))
    )
    (comp (ref "MEGA-A2")
      (value "Header-Male-2.54_1x8")
      (fields (field (name "Manufacturer Part") "B-2100S08P-A110") (field (name "Manufacturer") "Ckmtw(灿科盟)"))
      (libsource (lib "") (part "Header-Male-2.54_1x8"))
    )
    (comp (ref "MEGA-D1")
      (value "Header-Male-2.54_1x8")
      (fields (field (name "Manufacturer Part") "B-2100S08P-A110") (field (name "Manufacturer") "Ckmtw(灿科盟)"))
      (libsource (lib "") (part "Header-Male-2.54_1x8_2"))
    )
    (comp (ref "MEGA-D2")
      (value "Header-Male-2.54_1x8")
      (fields (field (name "Manufacturer Part") "B-2100S08P-A110") (field (name "Manufacturer") "Ckmtw(灿科盟)"))
      (libsource (lib "") (part "Header-Male-2.54_1x8_4"))
    )
    (comp (ref "MEGA-IOREF1")
      (value "Header-Male-2.54_1x8")
      (fields (field (name "Manufacturer Part") "B-2100S08P-A110") (field (name "Manufacturer") "Ckmtw(灿科盟)"))
      (libsource (lib "") (part "Header-Male-2.54_1x8_1"))
    )
    (comp (ref "MEGA-SCL2")
      (value "Header-Male-2.54_1x10")
      (fields (field (name "Manufacturer Part") "2.54-1*10P针") (field (name "Manufacturer") "BOOMELE(博穆精密)"))
      (libsource (lib "") (part "Header-Male-2.54_1x10"))
    )
    (comp (ref "MOTOR_POWER1")
      (value "DB126V-5.0-2P")
      (fields
        (field (name "Manufacturer Part") "DB126V-5.0-2P-GN-P")
        (field (name "Manufacturer") "DORABO(地博电气)")
      )
      (libsource (lib "") (part "DB126V-5.0-2P_2"))
    )
    (comp (ref "OXI_L1")
      (value "KH-2.54FH-1X8P-H8.5")
      (fields (field (name "Manufacturer") "kinghelm(金航标)"))
      (libsource (lib "") (part "KH-2.54FH-1X8P-H8.5_11"))
    )
    (comp (ref "OXI_M1")
      (value "2.54-1*4")
      (fields (field (name "Manufacturer") "ZHOURI(洲日)"))
      (libsource (lib "") (part "2.54-1*4_9"))
    )
    (comp (ref "OXI_M_C1")
      (value "100uF")
      (fields
        (field (name "Manufacturer Part") "50YXF100MEFCCE8X11.5")
        (field (name "Manufacturer") "rubycon(红宝石)")
      )
      (libsource (lib "") (part "50YXF100MEFCCE8X11.5_8"))
    )
    (comp (ref "OXI_R1")
      (value "KH-2.54FH-1X8P-H8.5")
      (fields (field (name "Manufacturer") "kinghelm(金航标)"))
      (libsource (lib "") (part "KH-2.54FH-1X8P-H8.5_6"))
    )
    (comp (ref "Q2")
      (value "TIP120")
      (fields (field (name "Manufacturer") "ST(意法半导体)"))
      (libsource (lib "") (part "TIP120"))
    )
    (comp (ref "R1")
      (value "100Ω")
      (fields
        (field (name "Manufacturer Part") "CMB02070X1000GB200")
        (field (name "Manufacturer") "VISHAY(威世)")
      )
      (libsource (lib "") (part "CMB02070X1000GB200"))
    )
    (comp (ref "R2")
      (value "100Ω")
      (fields
        (field (name "Manufacturer Part") "CMB02070X1000GB200")
        (field (name "Manufacturer") "VISHAY(威世)")
      )
      (libsource (lib "") (part "CMB02070X1000GB200_1"))
    )
    (comp (ref "R6")
      (value "2.2kΩ")
      (fields (field (name "Manufacturer Part") "RMC08052.2K1%N") (field (name "Manufacturer") "Tyohm(幸亚电阻)"))
      (libsource (lib "") (part "RMC08052.2K1%N"))
    )
    (comp (ref "SW1")
      (value "K2-1157SP-I4SW-04")
      (fields (field (name "Manufacturer Part") "K2-1157SP-I4SW-01") (field (name "Manufacturer") "韩国韩荣"))
      (libsource (lib "") (part "K2-1157SP-I4SW-04_1"))
    )
    (comp (ref "SW3")
      (value "K2-1157SP-I4SW-04")
      (fields (field (name "Manufacturer Part") "K2-1157SP-I4SW-01") (field (name "Manufacturer") "韩国韩荣"))
      (libsource (lib "") (part "K2-1157SP-I4SW-04"))
    )
    (comp (ref "U5")
      (value "CS-1109-1X18 (14.0)")
      (fields (field (name "Manufacturer") "CST(永丰盈)"))
      (libsource (lib "") (part "CS-1109-1X18 (14.0)_1"))
    )
    (comp (ref "U6")
      (value "DB126V-5.0-2P")
      (fields
        (field (name "Manufacturer Part") "DB126V-5.0-2P-GN-P")
        (field (name "Manufacturer") "DORABO(地博电气)")
      )
      (libsource (lib "") (part "DB126V-5.0-2P_3"))
    )
    (comp (ref "U7")
      (value "CS-1109-1X18 (14.0)")
      (fields (field (name "Manufacturer") "CST(永丰盈)"))
      (libsource (lib "") (part "CS-1109-1X18 (14.0)"))
    )
    (comp (ref "U29")
      (value "5kΩ")
      (fields
        (field (name "Manufacturer Part") "TR0603B5K00P0525Z")
        (field (name "Manufacturer") "EVER OHMS(天二科技)")
      )
      (libsource (lib "") (part "TR0603B5K00P0525Z_1"))
    )
    (comp (ref "U30")
      (value "5kΩ")
      (fields
        (field (name "Manufacturer Part") "TR0603B5K00P0525Z")
        (field (name "Manufacturer") "EVER OHMS(天二科技)")
      )
      (libsource (lib "") (part "TR0603B5K00P0525Z"))
    )
    (comp (ref "WASH_L1")
      (value "KH-2.54FH-1X8P-H8.5")
      (fields (field (name "Manufacturer") "kinghelm(金航标)"))
      (libsource (lib "") (part "KH-2.54FH-1X8P-H8.5"))
    )
    (comp (ref "WASH_M1")
      (value "2.54-1*4")
      (fields (field (name "Manufacturer") "ZHOURI(洲日)"))
      (libsource (lib "") (part "2.54-1*4_10"))
    )
    (comp (ref "WASH_M_C1")
      (value "100uF")
      (fields
        (field (name "Manufacturer Part") "50YXF100MEFCCE8X11.5")
        (field (name "Manufacturer") "rubycon(红宝石)")
      )
      (libsource (lib "") (part "50YXF100MEFCCE8X11.5_2"))
    )
    (comp (ref "WASH_R1")
      (value "KH-2.54FH-1X8P-H8.5")
      (fields (field (name "Manufacturer") "kinghelm(金航标)"))
      (libsource (lib "") (part "KH-2.54FH-1X8P-H8.5_2"))
    )
    (comp (ref "WASTE1_L")
      (value "KH-2.54FH-1X8P-H8.5")
      (fields (field (name "Manufacturer") "kinghelm(金航标)"))
      (libsource (lib "") (part "KH-2.54FH-1X8P-H8.5_18"))
    )
    (comp (ref "WASTE1_M")
      (value "2.54-1*4")
      (fields (field (name "Manufacturer") "ZHOURI(洲日)"))
      (libsource (lib "") (part "2.54-1*4_1"))
    )
    (comp (ref "WASTE1_R")
      (value "KH-2.54FH-1X8P-H8.5")
      (fields (field (name "Manufacturer") "kinghelm(金航标)"))
      (libsource (lib "") (part "KH-2.54FH-1X8P-H8.5_12"))
    )
    (comp (ref "WASTE2_L")
      (value "KH-2.54FH-1X8P-H8.5")
      (fields (field (name "Manufacturer") "kinghelm(金航标)"))
      (libsource (lib "") (part "KH-2.54FH-1X8P-H8.5_17"))
    )
    (comp (ref "WASTE2_M")
      (value "2.54-1*4")
      (fields (field (name "Manufacturer") "ZHOURI(洲日)"))
      (libsource (lib "") (part "2.54-1*4_2"))
    )
    (comp (ref "WASTE2_R")
      (value "KH-2.54FH-1X8P-H8.5")
      (fields (field (name "Manufacturer") "kinghelm(金航标)"))
      (libsource (lib "") (part "KH-2.54FH-1X8P-H8.5_20"))
    )
    (comp (ref "WASTE_M_C1")
      (value "100uF")
      (fields
        (field (name "Manufacturer Part") "50YXF100MEFCCE8X11.5")
        (field (name "Manufacturer") "rubycon(红宝石)")
      )
      (libsource (lib "") (part "50YXF100MEFCCE8X11.5_6"))
    )
    (comp (ref "WASTE_M_C2")
      (value "100uF")
      (fields
        (field (name "Manufacturer Part") "50YXF100MEFCCE8X11.5")
        (field (name "Manufacturer") "rubycon(红宝石)")
      )
      (libsource (lib "") (part "50YXF100MEFCCE8X11.5_6"))
    )
  )
  (nets
    (net (code "1") (name "5V") (class "Default")
      (node (ref "5V_POWER") (pin "1") (pinfunction "5V_1") (pintype "unspecified"))
      (node (ref "ACT_L1") (pin "2") (pinfunction "VDD_2") (pintype "unspecified"))
      (node (ref "ACT_PH_C6") (pin "1") (pinfunction "1_1") (pintype "input"))
      (node (ref "ACT_PRINTHEAD1") (pin "9") (pinfunction "VDD_9") (pintype "unspecified"))
      (node (ref "C1") (pin "1") (pinfunction "1_1") (pintype "unspecified"))
      (node (ref "DA_L1") (pin "2") (pinfunction "2_2") (pintype "unspecified"))
      (node (ref "DA_PH_C6") (pin "1") (pinfunction "1_1") (pintype "input"))
      (node (ref "DA_PRINTHEAD1") (pin "9") (pinfunction "VDD_9") (pintype "unspecified"))
      (node (ref "DC_L1") (pin "2") (pinfunction "2_2") (pintype "unspecified"))
      (node (ref "DC_PH_C6") (pin "1") (pinfunction "1_1") (pintype "input"))
      (node (ref "DC_PRINTHEAD1") (pin "9") (pinfunction "VDD_9") (pintype "unspecified"))
      (node (ref "DET_L1") (pin "2") (pinfunction "2_2") (pintype "unspecified"))
      (node (ref "DG_L1") (pin "2") (pinfunction "2_2") (pintype "unspecified"))
      (node (ref "DG_PH_C6") (pin "1") (pinfunction "1_1") (pintype "input"))
      (node (ref "DG_PRINTHEAD1") (pin "9") (pinfunction "VDD_9") (pintype "unspecified"))
      (node (ref "DT_L1") (pin "2") (pinfunction "2_2") (pintype "unspecified"))
      (node (ref "DT_PH_C6") (pin "1") (pinfunction "1_1") (pintype "input"))
      (node (ref "DT_PRINTHEAD1") (pin "9") (pinfunction "VDD_9") (pintype "unspecified"))
      (node (ref "H1") (pin "2") (pinfunction "2_2") (pintype "unspecified"))
      (node (ref "H1") (pin "4") (pinfunction "4_4") (pintype "unspecified"))
      (node (ref "H1") (pin "6") (pinfunction "6_6") (pintype "unspecified"))
      (node (ref "H14") (pin "2") (pinfunction "2_2") (pintype "unspecified"))
      (node (ref "H14") (pin "4") (pinfunction "4_4") (pintype "unspecified"))
      (node (ref "H14") (pin "6") (pinfunction "6_6") (pintype "unspecified"))
      (node (ref "H15") (pin "2") (pinfunction "2_2") (pintype "unspecified"))
      (node (ref "H15") (pin "4") (pinfunction "4_4") (pintype "unspecified"))
      (node (ref "H15") (pin "6") (pinfunction "6_6") (pintype "unspecified"))
      (node (ref "H16") (pin "2") (pinfunction "2_2") (pintype "unspecified"))
      (node (ref "H16") (pin "4") (pinfunction "4_4") (pintype "unspecified"))
      (node (ref "H16") (pin "6") (pinfunction "6_6") (pintype "unspecified"))
      (node (ref "H17") (pin "2") (pinfunction "2_2") (pintype "unspecified"))
      (node (ref "H17") (pin "4") (pinfunction "4_4") (pintype "unspecified"))
      (node (ref "H17") (pin "6") (pinfunction "6_6") (pintype "unspecified"))
      (node (ref "H18") (pin "2") (pinfunction "2_2") (pintype "unspecified"))
      (node (ref "H18") (pin "4") (pinfunction "4_4") (pintype "unspecified"))
      (node (ref "H18") (pin "6") (pinfunction "6_6") (pintype "unspecified"))
      (node (ref "H19") (pin "2") (pinfunction "2_2") (pintype "unspecified"))
      (node (ref "H19") (pin "4") (pinfunction "4_4") (pintype "unspecified"))
      (node (ref "H19") (pin "6") (pinfunction "6_6") (pintype "unspecified"))
      (node (ref "H2") (pin "2") (pinfunction "2_2") (pintype "unspecified"))
      (node (ref "H2") (pin "4") (pinfunction "4_4") (pintype "unspecified"))
      (node (ref "H2") (pin "6") (pinfunction "6_6") (pintype "unspecified"))
      (node (ref "H3") (pin "2") (pinfunction "2_2") (pintype "unspecified"))
      (node (ref "H3") (pin "4") (pinfunction "4_4") (pintype "unspecified"))
      (node (ref "H3") (pin "6") (pinfunction "6_6") (pintype "unspecified"))
      (node (ref "H4") (pin "2") (pinfunction "2_2") (pintype "unspecified"))
      (node (ref "H4") (pin "4") (pinfunction "4_4") (pintype "unspecified"))
      (node (ref "H4") (pin "6") (pinfunction "6_6") (pintype "unspecified"))
      (node (ref "H5") (pin "2") (pinfunction "2_2") (pintype "unspecified"))
      (node (ref "H5") (pin "4") (pinfunction "4_4") (pintype "unspecified"))
      (node (ref "H5") (pin "6") (pinfunction "6_6") (pintype "unspecified"))
      (node (ref "LIMIT_L1") (pin "1") (pinfunction "5V_1") (pintype "unspecified"))
      (node (ref "LIMIT_R1") (pin "1") (pinfunction "5V_1") (pintype "unspecified"))
      (node (ref "LINEAR_L1") (pin "2") (pinfunction "2_2") (pintype "unspecified"))
      (node (ref "OXI_L1") (pin "2") (pinfunction "2_2") (pintype "unspecified"))
      (node (ref "R1") (pin "1") (pinfunction "1_1") (pintype "unspecified"))
      (node (ref "R2") (pin "2") (pinfunction "2_2") (pintype "unspecified"))
      (node (ref "WASH_L1") (pin "2") (pinfunction "VDD_2") (pintype "unspecified"))
      (node (ref "WASTE1_L") (pin "2") (pinfunction "2_2") (pintype "unspecified"))
      (node (ref "WASTE2_L") (pin "2") (pinfunction "2_2") (pintype "unspecified"))
    )
    (net (code "2") (name "12V") (class "Default")
      (node (ref "ACT_S1") (pin "1") (pinfunction "12V_1") (pintype "unspecified"))
      (node (ref "D2") (pin "1") (pinfunction "1_1") (pintype "unspecified"))
      (node (ref "D4") (pin "1") (pinfunction "C_1") (pintype "unspecified"))
      (node (ref "DA_S1") (pin "1") (pinfunction "12V_1") (pintype "unspecified"))
      (node (ref "DC_S1") (pin "1") (pinfunction "12V_1") (pintype "unspecified"))
      (node (ref "DG_S1") (pin "1") (pinfunction "12V_1") (pintype "unspecified"))
      (node (ref "DT_S1") (pin "1") (pinfunction "12V_1") (pintype "unspecified"))
      (node (ref "H8") (pin "8") (pinfunction "VIN_8") (pintype "unspecified"))
      (node (ref "MEGA-IOREF1") (pin "8") (pinfunction "VIN_8") (pintype "unspecified"))
      (node (ref "U6") (pin "1") (pinfunction "12V_1") (pintype "unspecified"))
    )
    (net (code "3") (name "24V") (class "Default")
      (node (ref "D5") (pin "1") (pinfunction "C_1") (pintype "unspecified"))
    )
    (net (code "4") (name "ACT_PH_VPPH") (class "Default")
      (node (ref "ACT_PH_M2") (pin "2") (pinfunction "D_2") (pintype "unspecified"))
      (node (ref "ACT_PRINTHEAD1") (pin "3") (pinfunction "VPPH_3") (pintype "unspecified"))
    )
    (net (code "5") (name "ACT_PH_VPPL") (class "Default")
      (node (ref "ACT_PH_M1") (pin "2") (pinfunction "D_2") (pintype "unspecified"))
      (node (ref "ACT_PRINTHEAD1") (pin "4") (pinfunction "VPPL_4") (pintype "unspecified"))
    )
    (net (code "6") (name "ACT_PH_fault") (class "Default")
      (node (ref "ACT_PRINTHEAD1") (pin "6") (pinfunction "FAULT_6") (pintype "unspecified"))
      (node (ref "U5") (pin "3") (pinfunction "24_3") (pintype "unspecified"))
    )
    (net (code "7") (name "ACT_PH_fire") (class "Default")
      (node (ref "ACT_PRINTHEAD1") (pin "16") (pinfunction "FIRE_16") (pintype "unspecified"))
      (node (ref "U7") (pin "16") (pinfunction "25_16") (pintype "unspecified"))
    )
    (net (code "8") (name "ACT_PH_nSS1") (class "Default")
      (node (ref "ACT_PRINTHEAD1") (pin "12") (pinfunction "nSS1_12") (pintype "unspecified"))
      (node (ref "U5") (pin "2") (pinfunction "22_2") (pintype "unspecified"))
    )
    (net (code "9") (name "ACT_PH_nSS2") (class "Default")
      (node (ref "ACT_PRINTHEAD1") (pin "1") (pinfunction "nSS2_1") (pintype "unspecified"))
      (node (ref "U7") (pin "17") (pinfunction "23_17") (pintype "unspecified"))
    )
    (net (code "10") (name "ACT_PH_ready") (class "Default")
      (node (ref "ACT_PRINTHEAD1") (pin "14") (pinfunction "READY_14") (pintype "unspecified"))
      (node (ref "U5") (pin "4") (pinfunction "26_4") (pintype "unspecified"))
    )
    (net (code "11") (name "ACT_S") (class "Default")
      (node (ref "ACT_S_R1") (pin "2") (pinfunction "2_2") (pintype "unspecified"))
      (node (ref "ACT_S_R2") (pin "1") (pinfunction "1_1") (pintype "unspecified"))
      (node (ref "H9") (pin "1") (pinfunction "A0_1") (pintype "input"))
    )
    (net (code "12") (name "ACT_enable") (class "Default")
      (node (ref "ACT_R1") (pin "8") (pinfunction "8_8") (pintype "unspecified"))
      (node (ref "H7") (pin "8") (pinfunction "0_8") (pintype "unspecified"))
    )
    (net (code "13") (name "ACT_step") (class "Default")
      (node (ref "ACT_R1") (pin "2") (pinfunction "2_2") (pintype "unspecified"))
      (node (ref "H7") (pin "3") (pinfunction "5_3") (pintype "unspecified"))
    )
    (net (code "14") (name "DET_E") (class "Default")
      (node (ref "MEGA-SCL2") (pin "8") (pinfunction "10_8") (pintype "unspecified"))
    )
    (net (code "15") (name "DET_enable") (class "Default")
      (node (ref "DET_R1") (pin "8") (pinfunction "8_8") (pintype "unspecified"))
    )
    (net (code "16") (name "DET_pulse") (class "Default")
      (node (ref "MEGA-D1") (pin "4") (pinfunction "4_4") (pintype "unspecified"))
    )
    (net (code "17") (name "DET_step") (class "Default")
      (node (ref "DET_R1") (pin "2") (pinfunction "2_2") (pintype "unspecified"))
    )
    (net (code "18") (name "DIR") (class "Default")
      (node (ref "MEGA-D1") (pin "1") (pinfunction "7_1") (pintype "unspecified"))
    )
    (net (code "19") (name "GND") (class "Default")
      (node (ref "12V_POWER") (pin "2") (pinfunction "GND_2") (pintype "unspecified"))
      (node (ref "5V_POWER") (pin "2") (pinfunction "GND_2") (pintype "unspecified"))
      (node (ref "ACT_L1") (pin "1") (pinfunction "GND_1") (pintype "unspecified"))
      (node (ref "ACT_L1") (pin "7") (pinfunction "GND_7") (pintype "unspecified"))
      (node (ref "ACT_M_C1") (pin "2") (pinfunction "2_2") (pintype "unspecified"))
      (node (ref "ACT_PH_C1") (pin "2") (pinfunction "2_2") (pintype "input"))
      (node (ref "ACT_PH_C2") (pin "2") (pinfunction "2_2") (pintype "unspecified"))
      (node (ref "ACT_PH_C3") (pin "1") (pinfunction "1_1") (pintype "input"))
      (node (ref "ACT_PH_C4") (pin "1") (pinfunction "1_1") (pintype "unspecified"))
      (node (ref "ACT_PH_C5") (pin "2") (pinfunction "2_2") (pintype "input"))
      (node (ref "ACT_PH_C6") (pin "2") (pinfunction "2_2") (pintype "input"))
      (node (ref "ACT_PH_R2") (pin "1") (pinfunction "1_1") (pintype "unspecified"))
      (node (ref "ACT_PH_R4") (pin "1") (pinfunction "1_1") (pintype "unspecified"))
      (node (ref "ACT_PRINTHEAD1") (pin "10") (pinfunction "GND_10") (pintype "unspecified"))
      (node (ref "ACT_PRINTHEAD1") (pin "2") (pinfunction "GNDH_2") (pintype "unspecified"))
      (node (ref "ACT_PRINTHEAD1") (pin "5") (pinfunction "GNDL_5") (pintype "unspecified"))
      (node (ref "ACT_S1") (pin "2") (pinfunction "GND_2") (pintype "unspecified"))
      (node (ref "ACT_S_R2") (pin "2") (pinfunction "2_2") (pintype "unspecified"))
      (node (ref "C1") (pin "2") (pinfunction "2_2") (pintype "unspecified"))
      (node (ref "DA_L1") (pin "1") (pinfunction "1_1") (pintype "unspecified"))
      (node (ref "DA_L1") (pin "7") (pinfunction "7_7") (pintype "unspecified"))
      (node (ref "DA_M_C1") (pin "2") (pinfunction "2_2") (pintype "unspecified"))
      (node (ref "DA_PH_C1") (pin "2") (pinfunction "2_2") (pintype "input"))
      (node (ref "DA_PH_C2") (pin "2") (pinfunction "2_2") (pintype "unspecified"))
      (node (ref "DA_PH_C3") (pin "1") (pinfunction "1_1") (pintype "input"))
      (node (ref "DA_PH_C4") (pin "1") (pinfunction "1_1") (pintype "unspecified"))
      (node (ref "DA_PH_C5") (pin "2") (pinfunction "2_2") (pintype "input"))
      (node (ref "DA_PH_C6") (pin "2") (pinfunction "2_2") (pintype "input"))
      (node (ref "DA_PH_R2") (pin "1") (pinfunction "1_1") (pintype "unspecified"))
      (node (ref "DA_PH_R4") (pin "1") (pinfunction "1_1") (pintype "unspecified"))
      (node (ref "DA_PRINTHEAD1") (pin "10") (pinfunction "GND_10") (pintype "unspecified"))
      (node (ref "DA_PRINTHEAD1") (pin "2") (pinfunction "GNDH_2") (pintype "unspecified"))
      (node (ref "DA_PRINTHEAD1") (pin "5") (pinfunction "GNDL_5") (pintype "unspecified"))
      (node (ref "DA_S1") (pin "2") (pinfunction "GND_2") (pintype "unspecified"))
      (node (ref "DA_S_R2") (pin "2") (pinfunction "2_2") (pintype "unspecified"))
      (node (ref "DC_L1") (pin "1") (pinfunction "1_1") (pintype "unspecified"))
      (node (ref "DC_L1") (pin "7") (pinfunction "7_7") (pintype "unspecified"))
      (node (ref "DC_M_C1") (pin "2") (pinfunction "2_2") (pintype "unspecified"))
      (node (ref "DC_PH_C2") (pin "2") (pinfunction "2_2") (pintype "unspecified"))
      (node (ref "DC_PH_C3") (pin "1") (pinfunction "1_1") (pintype "input"))
      (node (ref "DC_PH_C4") (pin "1") (pinfunction "1_1") (pintype "unspecified"))
      (node (ref "DC_PH_C5") (pin "2") (pinfunction "2_2") (pintype "input"))
      (node (ref "DC_PH_C6") (pin "2") (pinfunction "2_2") (pintype "input"))
      (node (ref "DC_PH_C7") (pin "2") (pinfunction "2_2") (pintype "input"))
      (node (ref "DC_PH_R2") (pin "1") (pinfunction "1_1") (pintype "unspecified"))
      (node (ref "DC_PH_R4") (pin "1") (pinfunction "1_1") (pintype "unspecified"))
      (node (ref "DC_PRINTHEAD1") (pin "10") (pinfunction "GND_10") (pintype "unspecified"))
      (node (ref "DC_PRINTHEAD1") (pin "2") (pinfunction "GNDH_2") (pintype "unspecified"))
      (node (ref "DC_PRINTHEAD1") (pin "5") (pinfunction "GNDL_5") (pintype "unspecified"))
      (node (ref "DC_S1") (pin "2") (pinfunction "GND_2") (pintype "unspecified"))
      (node (ref "DC_S_R2") (pin "2") (pinfunction "2_2") (pintype "unspecified"))
      (node (ref "DET_L1") (pin "1") (pinfunction "1_1") (pintype "unspecified"))
      (node (ref "DET_L1") (pin "7") (pinfunction "7_7") (pintype "unspecified"))
      (node (ref "DET_M_C1") (pin "2") (pinfunction "2_2") (pintype "unspecified"))
      (node (ref "DG_L1") (pin "1") (pinfunction "1_1") (pintype "unspecified"))
      (node (ref "DG_L1") (pin "7") (pinfunction "7_7") (pintype "unspecified"))
      (node (ref "DG_M_C1") (pin "2") (pinfunction "2_2") (pintype "unspecified"))
      (node (ref "DG_PH_C1") (pin "2") (pinfunction "2_2") (pintype "input"))
      (node (ref "DG_PH_C2") (pin "2") (pinfunction "2_2") (pintype "unspecified"))
      (node (ref "DG_PH_C3") (pin "1") (pinfunction "1_1") (pintype "input"))
      (node (ref "DG_PH_C4") (pin "1") (pinfunction "1_1") (pintype "unspecified"))
      (node (ref "DG_PH_C5") (pin "2") (pinfunction "2_2") (pintype "input"))
      (node (ref "DG_PH_C6") (pin "2") (pinfunction "2_2") (pintype "input"))
      (node (ref "DG_PH_R2") (pin "1") (pinfunction "1_1") (pintype "unspecified"))
      (node (ref "DG_PH_R4") (pin "1") (pinfunction "1_1") (pintype "unspecified"))
      (node (ref "DG_PRINTHEAD1") (pin "10") (pinfunction "GND_10") (pintype "unspecified"))
      (node (ref "DG_PRINTHEAD1") (pin "2") (pinfunction "GNDH_2") (pintype "unspecified"))
      (node (ref "DG_PRINTHEAD1") (pin "5") (pinfunction "GNDL_5") (pintype "unspecified"))
      (node (ref "DG_S1") (pin "2") (pinfunction "GND_2") (pintype "unspecified"))
      (node (ref "DG_S_R2") (pin "2") (pinfunction "2_2") (pintype "unspecified"))
      (node (ref "DT_L1") (pin "1") (pinfunction "1_1") (pintype "unspecified"))
      (node (ref "DT_L1") (pin "7") (pinfunction "7_7") (pintype "unspecified"))
      (node (ref "DT_M_C1") (pin "2") (pinfunction "2_2") (pintype "unspecified"))
      (node (ref "DT_PH_C1") (pin "2") (pinfunction "2_2") (pintype "input"))
      (node (ref "DT_PH_C2") (pin "2") (pinfunction "2_2") (pintype "unspecified"))
      (node (ref "DT_PH_C3") (pin "1") (pinfunction "1_1") (pintype "input"))
      (node (ref "DT_PH_C4") (pin "1") (pinfunction "1_1") (pintype "unspecified"))
      (node (ref "DT_PH_C5") (pin "2") (pinfunction "2_2") (pintype "input"))
      (node (ref "DT_PH_C6") (pin "2") (pinfunction "2_2") (pintype "input"))
      (node (ref "DT_PH_R2") (pin "1") (pinfunction "1_1") (pintype "unspecified"))
      (node (ref "DT_PH_R4") (pin "1") (pinfunction "1_1") (pintype "unspecified"))
      (node (ref "DT_PRINTHEAD1") (pin "10") (pinfunction "GND_10") (pintype "unspecified"))
      (node (ref "DT_PRINTHEAD1") (pin "2") (pinfunction "GNDH_2") (pintype "unspecified"))
      (node (ref "DT_PRINTHEAD1") (pin "5") (pinfunction "GNDL_5") (pintype "unspecified"))
      (node (ref "DT_S1") (pin "2") (pinfunction "GND_2") (pintype "unspecified"))
      (node (ref "DT_S_R2") (pin "2") (pinfunction "2_2") (pintype "unspecified"))
      (node (ref "H6") (pin "4") (pinfunction "GND_4") (pintype "unspecified"))
      (node (ref "H8") (pin "6") (pinfunction "GND_6") (pintype "unspecified"))
      (node (ref "H8") (pin "7") (pinfunction "GND_7") (pintype "unspecified"))
      (node (ref "LIMIT_L1") (pin "2") (pinfunction "GND_2") (pintype "unspecified"))
      (node (ref "LIMIT_R1") (pin "2") (pinfunction "GND_2") (pintype "unspecified"))
      (node (ref "LINEAR_L1") (pin "1") (pinfunction "1_1") (pintype "unspecified"))
      (node (ref "LINEAR_L1") (pin "7") (pinfunction "7_7") (pintype "unspecified"))
      (node (ref "LINEAR_M_C1") (pin "2") (pinfunction "2_2") (pintype "unspecified"))
      (node (ref "MEGA-IOREF1") (pin "6") (pinfunction "GND_6") (pintype "unspecified"))
      (node (ref "MEGA-IOREF1") (pin "7") (pinfunction "GND_7") (pintype "unspecified"))
      (node (ref "MEGA-SCL2") (pin "4") (pinfunction "GND_4") (pintype "unspecified"))
      (node (ref "MOTOR_POWER1") (pin "2") (pinfunction "GND_2") (pintype "unspecified"))
      (node (ref "OXI_L1") (pin "1") (pinfunction "1_1") (pintype "unspecified"))
      (node (ref "OXI_L1") (pin "7") (pinfunction "7_7") (pintype "unspecified"))
      (node (ref "OXI_M_C1") (pin "2") (pinfunction "2_2") (pintype "unspecified"))
      (node (ref "Q2") (pin "3") (pinfunction "E_3") (pintype "input"))
      (node (ref "U29") (pin "2") (pinfunction "2_2") (pintype "unspecified"))
      (node (ref "U30") (pin "1") (pinfunction "1_1") (pintype "unspecified"))
      (node (ref "U5") (pin "18") (pinfunction "GND_18") (pintype "unspecified"))
      (node (ref "U7") (pin "1") (pinfunction "GND_1") (pintype "unspecified"))
      (node (ref "WASH_L1") (pin "1") (pinfunction "GND_1") (pintype "unspecified"))
      (node (ref "WASH_L1") (pin "7") (pinfunction "GND_7") (pintype "unspecified"))
      (node (ref "WASH_M_C1") (pin "2") (pinfunction "2_2") (pintype "unspecified"))
      (node (ref "WASTE1_L") (pin "1") (pinfunction "1_1") (pintype "unspecified"))
      (node (ref "WASTE1_L") (pin "7") (pinfunction "7_7") (pintype "unspecified"))
      (node (ref "WASTE1_R") (pin "1") (pinfunction "1_1") (pintype "unspecified"))
      (node (ref "WASTE2_L") (pin "1") (pinfunction "1_1") (pintype "unspecified"))
      (node (ref "WASTE2_L") (pin "7") (pinfunction "7_7") (pintype "unspecified"))
      (node (ref "WASTE2_R") (pin "1") (pinfunction "1_1") (pintype "unspecified"))
      (node (ref "WASTE_M_C1") (pin "2") (pinfunction "2_2") (pintype "unspecified"))
      (node (ref "WASTE_M_C2") (pin "2") (pinfunction "2_2") (pintype "unspecified"))
    )
    (net (code "20") (name "LIMIT_L_S") (class "Default")
      (node (ref "LIMIT_L1") (pin "3") (pinfunction "S_3") (pintype "unspecified"))
      (node (ref "U30") (pin "2") (pinfunction "2_2") (pintype "unspecified"))
    )
    (net (code "21") (name "LIMIT_R_S") (class "Default")
      (node (ref "LIMIT_R1") (pin "3") (pinfunction "S_3") (pintype "unspecified"))
      (node (ref "U29") (pin "1") (pinfunction "1_1") (pintype "unspecified"))
    )
    (net (code "22") (name "M_35V") (class "Default")
      (node (ref "ACT_L1") (pin "8") (pinfunction "VMOT_8") (pintype "unspecified"))
      (node (ref "ACT_M_C1") (pin "1") (pinfunction "1_1") (pintype "unspecified"))
      (node (ref "DA_L1") (pin "8") (pinfunction "8_8") (pintype "unspecified"))
      (node (ref "DA_M_C1") (pin "1") (pinfunction "1_1") (pintype "unspecified"))
      (node (ref "DC_L1") (pin "8") (pinfunction "8_8") (pintype "unspecified"))
      (node (ref "DC_M_C1") (pin "1") (pinfunction "1_1") (pintype "unspecified"))
      (node (ref "DET_L1") (pin "8") (pinfunction "8_8") (pintype "unspecified"))
      (node (ref "DET_M_C1") (pin "1") (pinfunction "1_1") (pintype "unspecified"))
      (node (ref "DG_L1") (pin "8") (pinfunction "8_8") (pintype "unspecified"))
      (node (ref "DG_M_C1") (pin "1") (pinfunction "1_1") (pintype "unspecified"))
      (node (ref "DT_L1") (pin "8") (pinfunction "8_8") (pintype "unspecified"))
      (node (ref "DT_M_C1") (pin "1") (pinfunction "1_1") (pintype "unspecified"))
      (node (ref "LINEAR_L1") (pin "8") (pinfunction "8_8") (pintype "unspecified"))
      (node (ref "LINEAR_M_C1") (pin "1") (pinfunction "1_1") (pintype "unspecified"))
      (node (ref "OXI_L1") (pin "8") (pinfunction "8_8") (pintype "unspecified"))
      (node (ref "OXI_M_C1") (pin "1") (pinfunction "1_1") (pintype "unspecified"))
      (node (ref "WASH_L1") (pin "8") (pinfunction "VMOT_8") (pintype "unspecified"))
      (node (ref "WASH_M_C1") (pin "1") (pinfunction "1_1") (pintype "unspecified"))
      (node (ref "WASTE1_L") (pin "8") (pinfunction "8_8") (pintype "unspecified"))
      (node (ref "WASTE2_L") (pin "8") (pinfunction "8_8") (pintype "unspecified"))
      (node (ref "WASTE_M_C1") (pin "1") (pinfunction "1_1") (pintype "unspecified"))
      (node (ref "WASTE_M_C2") (pin "1") (pinfunction "1_1") (pintype "unspecified"))
    )
    (net (code "23") (name "Net-(12V_POWER-12V)") (class "Default")
      (node (ref "12V_POWER") (pin "1") (pinfunction "12V_1") (pintype "unspecified"))
      (node (ref "D4") (pin "2") (pinfunction "A_2") (pintype "unspecified"))
    )
    (net (code "24") (name "Net-(ACT_L1-A1)") (class "Default")
      (node (ref "ACT_L1") (pin "4") (pinfunction "A1_4") (pintype "unspecified"))
      (node (ref "ACT_M1") (pin "3") (pinfunction "3_3") (pintype "unspecified"))
    )
    (net (code "25") (name "Net-(ACT_L1-A2)") (class "Default")
      (node (ref "ACT_L1") (pin "5") (pinfunction "A2_5") (pintype "unspecified"))
      (node (ref "ACT_M1") (pin "2") (pinfunction "2_2") (pintype "unspecified"))
    )
    (net (code "26") (name "Net-(ACT_L1-B1)") (class "Default")
      (node (ref "ACT_L1") (pin "3") (pinfunction "B1_3") (pintype "unspecified"))
      (node (ref "ACT_M1") (pin "4") (pinfunction "4_4") (pintype "unspecified"))
    )
    (net (code "27") (name "Net-(ACT_L1-B2)") (class "Default")
      (node (ref "ACT_L1") (pin "6") (pinfunction "B2_6") (pintype "unspecified"))
      (node (ref "ACT_M1") (pin "1") (pinfunction "1_1") (pintype "unspecified"))
    )
    (net (code "28") (name "Net-(ACT_PH_D1-K)") (class "Default")
      (node (ref "ACT_PH_C1") (pin "1") (pinfunction "1_1") (pintype "input"))
      (node (ref "ACT_PH_C2") (pin "1") (pinfunction "1_1") (pintype "unspecified"))
      (node (ref "ACT_PH_C3") (pin "2") (pinfunction "2_2") (pintype "input"))
      (node (ref "ACT_PH_C4") (pin "2") (pinfunction "2_2") (pintype "unspecified"))
      (node (ref "ACT_PH_D1") (pin "1") (pinfunction "K_1") (pintype "unspecified"))
      (node (ref "ACT_PH_M1") (pin "3") (pinfunction "S_3") (pintype "unspecified"))
      (node (ref "ACT_PH_R1") (pin "1") (pinfunction "1_1") (pintype "unspecified"))
      (node (ref "ACT_PH_ZD1") (pin "1") (pinfunction "1_1") (pintype "unspecified"))
    )
    (net (code "29") (name "Net-(ACT_PH_D2-K)") (class "Default")
      (node (ref "ACT_PH_C5") (pin "1") (pinfunction "1_1") (pintype "input"))
      (node (ref "ACT_PH_D2") (pin "1") (pinfunction "K_1") (pintype "unspecified"))
      (node (ref "ACT_PH_M2") (pin "3") (pinfunction "S_3") (pintype "unspecified"))
      (node (ref "ACT_PH_R3") (pin "1") (pinfunction "1_1") (pintype "unspecified"))
      (node (ref "ACT_PH_ZD2") (pin "1") (pinfunction "1_1") (pintype "unspecified"))
    )
    (net (code "30") (name "Net-(ACT_PH_M1-G)") (class "Default")
      (node (ref "ACT_PH_M1") (pin "1") (pinfunction "G_1") (pintype "unspecified"))
      (node (ref "ACT_PH_R1") (pin "2") (pinfunction "2_2") (pintype "unspecified"))
      (node (ref "ACT_PH_T1") (pin "1") (pinfunction "C_1") (pintype "unspecified"))
      (node (ref "ACT_PH_ZD1") (pin "2") (pinfunction "2_2") (pintype "unspecified"))
    )
    (net (code "31") (name "Net-(ACT_PH_M2-G)") (class "Default")
      (node (ref "ACT_PH_M2") (pin "1") (pinfunction "G_1") (pintype "unspecified"))
      (node (ref "ACT_PH_R3") (pin "2") (pinfunction "2_2") (pintype "unspecified"))
      (node (ref "ACT_PH_T2") (pin "1") (pinfunction "C_1") (pintype "unspecified"))
      (node (ref "ACT_PH_ZD2") (pin "2") (pinfunction "2_2") (pintype "unspecified"))
    )
    (net (code "32") (name "Net-(ACT_PH_T1-E)") (class "Default")
      (node (ref "ACT_PH_R2") (pin "2") (pinfunction "2_2") (pintype "unspecified"))
      (node (ref "ACT_PH_T1") (pin "3") (pinfunction "E_3") (pintype "unspecified"))
    )
    (net (code "33") (name "Net-(ACT_PH_T2-E)") (class "Default")
      (node (ref "ACT_PH_R4") (pin "2") (pinfunction "2_2") (pintype "unspecified"))
      (node (ref "ACT_PH_T2") (pin "3") (pinfunction "E_3") (pintype "unspecified"))
    )
    (net (code "34") (name "Net-(ACT_R1-Pad3)") (class "Default")
      (node (ref "ACT_R1") (pin "3") (pinfunction "3_3") (pintype "unspecified"))
      (node (ref "ACT_R1") (pin "4") (pinfunction "4_4") (pintype "unspecified"))
    )
    (net (code "35") (name "Net-(ACT_R1-Pad5)") (class "Default")
      (node (ref "ACT_R1") (pin "5") (pinfunction "5_5") (pintype "unspecified"))
      (node (ref "H5") (pin "1") (pinfunction "1_1") (pintype "unspecified"))
    )
    (net (code "36") (name "Net-(ACT_R1-Pad6)") (class "Default")
      (node (ref "ACT_R1") (pin "6") (pinfunction "6_6") (pintype "unspecified"))
      (node (ref "H5") (pin "3") (pinfunction "3_3") (pintype "unspecified"))
    )
    (net (code "37") (name "Net-(ACT_R1-Pad7)") (class "Default")
      (node (ref "ACT_R1") (pin "7") (pinfunction "7_7") (pintype "unspecified"))
      (node (ref "H5") (pin "5") (pinfunction "5_5") (pintype "unspecified"))
    )
    (net (code "38") (name "Net-(ACT_S1-S)") (class "Default")
      (node (ref "ACT_S1") (pin "3") (pinfunction "S_3") (pintype "unspecified"))
      (node (ref "ACT_S_R1") (pin "1") (pinfunction "1_1") (pintype "unspecified"))
    )
    (net (code "39") (name "Net-(D5-A)") (class "Default")
      (node (ref "D5") (pin "2") (pinfunction "A_2") (pintype "unspecified"))
      (node (ref "MOTOR_POWER1") (pin "1") (pinfunction "24V_1") (pintype "unspecified"))
    )
    (net (code "40") (name "Net-(DA_L1-Pad3)") (class "Default")
      (node (ref "DA_L1") (pin "3") (pinfunction "3_3") (pintype "unspecified"))
      (node (ref "DA_M1") (pin "4") (pinfunction "4_4") (pintype "unspecified"))
    )
    (net (code "41") (name "Net-(DA_L1-Pad4)") (class "Default")
      (node (ref "DA_L1") (pin "4") (pinfunction "4_4") (pintype "unspecified"))
      (node (ref "DA_M1") (pin "3") (pinfunction "3_3") (pintype "unspecified"))
    )
    (net (code "42") (name "Net-(DA_L1-Pad5)") (class "Default")
      (node (ref "DA_L1") (pin "5") (pinfunction "5_5") (pintype "unspecified"))
      (node (ref "DA_M1") (pin "2") (pinfunction "2_2") (pintype "unspecified"))
    )
    (net (code "43") (name "Net-(DA_L1-Pad6)") (class "Default")
      (node (ref "DA_L1") (pin "6") (pinfunction "6_6") (pintype "unspecified"))
      (node (ref "DA_M1") (pin "1") (pinfunction "1_1") (pintype "unspecified"))
    )
    (net (code "44") (name "Net-(DA_PH_D1-K)") (class "Default")
      (node (ref "DA_PH_C1") (pin "1") (pinfunction "1_1") (pintype "input"))
      (node (ref "DA_PH_C2") (pin "1") (pinfunction "1_1") (pintype "unspecified"))
      (node (ref "DA_PH_C3") (pin "2") (pinfunction "2_2") (pintype "input"))
      (node (ref "DA_PH_C4") (pin "2") (pinfunction "2_2") (pintype "unspecified"))
      (node (ref "DA_PH_D1") (pin "1") (pinfunction "K_1") (pintype "unspecified"))
      (node (ref "DA_PH_M1") (pin "3") (pinfunction "S_3") (pintype "unspecified"))
      (node (ref "DA_PH_R1") (pin "1") (pinfunction "1_1") (pintype "unspecified"))
      (node (ref "DA_PH_ZD1") (pin "1") (pinfunction "1_1") (pintype "unspecified"))
    )
    (net (code "45") (name "Net-(DA_PH_D2-K)") (class "Default")
      (node (ref "DA_PH_C5") (pin "1") (pinfunction "1_1") (pintype "input"))
      (node (ref "DA_PH_D2") (pin "1") (pinfunction "K_1") (pintype "unspecified"))
      (node (ref "DA_PH_M2") (pin "3") (pinfunction "S_3") (pintype "unspecified"))
      (node (ref "DA_PH_R3") (pin "1") (pinfunction "1_1") (pintype "unspecified"))
      (node (ref "DA_PH_ZD2") (pin "1") (pinfunction "1_1") (pintype "unspecified"))
    )
    (net (code "46") (name "Net-(DA_PH_M1-G)") (class "Default")
      (node (ref "DA_PH_M1") (pin "1") (pinfunction "G_1") (pintype "unspecified"))
      (node (ref "DA_PH_R1") (pin "2") (pinfunction "2_2") (pintype "unspecified"))
      (node (ref "DA_PH_T1") (pin "1") (pinfunction "C_1") (pintype "unspecified"))
      (node (ref "DA_PH_ZD1") (pin "2") (pinfunction "2_2") (pintype "unspecified"))
    )
    (net (code "47") (name "Net-(DA_PH_M2-G)") (class "Default")
      (node (ref "DA_PH_M2") (pin "1") (pinfunction "G_1") (pintype "unspecified"))
      (node (ref "DA_PH_R3") (pin "2") (pinfunction "2_2") (pintype "unspecified"))
      (node (ref "DA_PH_T2") (pin "1") (pinfunction "C_1") (pintype "unspecified"))
      (node (ref "DA_PH_ZD2") (pin "2") (pinfunction "2_2") (pintype "unspecified"))
    )
    (net (code "48") (name "Net-(DA_PH_T1-E)") (class "Default")
      (node (ref "DA_PH_R2") (pin "2") (pinfunction "2_2") (pintype "unspecified"))
      (node (ref "DA_PH_T1") (pin "3") (pinfunction "E_3") (pintype "unspecified"))
    )
    (net (code "49") (name "Net-(DA_PH_T2-E)") (class "Default")
      (node (ref "DA_PH_R4") (pin "2") (pinfunction "2_2") (pintype "unspecified"))
      (node (ref "DA_PH_T2") (pin "3") (pinfunction "E_3") (pintype "unspecified"))
    )
    (net (code "50") (name "Net-(DA_R1-Pad3)") (class "Default")
      (node (ref "DA_R1") (pin "3") (pinfunction "3_3") (pintype "unspecified"))
      (node (ref "DA_R1") (pin "4") (pinfunction "4_4") (pintype "unspecified"))
    )
    (net (code "51") (name "Net-(DA_R1-Pad5)") (class "Default")
      (node (ref "DA_R1") (pin "5") (pinfunction "5_5") (pintype "unspecified"))
      (node (ref "H1") (pin "1") (pinfunction "1_1") (pintype "unspecified"))
    )
    (net (code "52") (name "Net-(DA_R1-Pad6)") (class "Default")
      (node (ref "DA_R1") (pin "6") (pinfunction "6_6") (pintype "unspecified"))
      (node (ref "H1") (pin "3") (pinfunction "3_3") (pintype "unspecified"))
    )
    (net (code "53") (name "Net-(DA_R1-Pad7)") (class "Default")
      (node (ref "DA_R1") (pin "7") (pinfunction "7_7") (pintype "unspecified"))
      (node (ref "H1") (pin "5") (pinfunction "5_5") (pintype "unspecified"))
    )
    (net (code "54") (name "Net-(DA_S1-S)") (class "Default")
      (node (ref "DA_S1") (pin "3") (pinfunction "S_3") (pintype "unspecified"))
      (node (ref "DA_S_R1") (pin "1") (pinfunction "1_1") (pintype "unspecified"))
    )
    (net (code "55") (name "Net-(DC_L1-Pad3)") (class "Default")
      (node (ref "DC_L1") (pin "3") (pinfunction "3_3") (pintype "unspecified"))
      (node (ref "DC_M1") (pin "4") (pinfunction "4_4") (pintype "unspecified"))
    )
    (net (code "56") (name "Net-(DC_L1-Pad4)") (class "Default")
      (node (ref "DC_L1") (pin "4") (pinfunction "4_4") (pintype "unspecified"))
      (node (ref "DC_M1") (pin "3") (pinfunction "3_3") (pintype "unspecified"))
    )
    (net (code "57") (name "Net-(DC_L1-Pad5)") (class "Default")
      (node (ref "DC_L1") (pin "5") (pinfunction "5_5") (pintype "unspecified"))
      (node (ref "DC_M1") (pin "2") (pinfunction "2_2") (pintype "unspecified"))
    )
    (net (code "58") (name "Net-(DC_L1-Pad6)") (class "Default")
      (node (ref "DC_L1") (pin "6") (pinfunction "6_6") (pintype "unspecified"))
      (node (ref "DC_M1") (pin "1") (pinfunction "1_1") (pintype "unspecified"))
    )
    (net (code "59") (name "Net-(DC_PH_D1-K)") (class "Default")
      (node (ref "DC_PH_C2") (pin "1") (pinfunction "1_1") (pintype "unspecified"))
      (node (ref "DC_PH_C3") (pin "2") (pinfunction "2_2") (pintype "input"))
      (node (ref "DC_PH_C4") (pin "2") (pinfunction "2_2") (pintype "unspecified"))
      (node (ref "DC_PH_C7") (pin "1") (pinfunction "1_1") (pintype "input"))
      (node (ref "DC_PH_D1") (pin "1") (pinfunction "K_1") (pintype "unspecified"))
      (node (ref "DC_PH_M1") (pin "3") (pinfunction "S_3") (pintype "unspecified"))
      (node (ref "DC_PH_R1") (pin "1") (pinfunction "1_1") (pintype "unspecified"))
      (node (ref "DC_PH_ZD1") (pin "1") (pinfunction "1_1") (pintype "unspecified"))
    )
    (net (code "60") (name "Net-(DC_PH_D2-K)") (class "Default")
      (node (ref "DC_PH_C5") (pin "1") (pinfunction "1_1") (pintype "input"))
      (node (ref "DC_PH_D2") (pin "1") (pinfunction "K_1") (pintype "unspecified"))
      (node (ref "DC_PH_M2") (pin "3") (pinfunction "S_3") (pintype "unspecified"))
      (node (ref "DC_PH_R3") (pin "1") (pinfunction "1_1") (pintype "unspecified"))
      (node (ref "DC_PH_ZD2") (pin "1") (pinfunction "1_1") (pintype "unspecified"))
    )
    (net (code "61") (name "Net-(DC_PH_M1-G)") (class "Default")
      (node (ref "DC_PH_M1") (pin "1") (pinfunction "G_1") (pintype "unspecified"))
      (node (ref "DC_PH_R1") (pin "2") (pinfunction "2_2") (pintype "unspecified"))
      (node (ref "DC_PH_T1") (pin "1") (pinfunction "C_1") (pintype "unspecified"))
      (node (ref "DC_PH_ZD1") (pin "2") (pinfunction "2_2") (pintype "unspecified"))
    )
    (net (code "62") (name "Net-(DC_PH_M2-G)") (class "Default")
      (node (ref "DC_PH_M2") (pin "1") (pinfunction "G_1") (pintype "unspecified"))
      (node (ref "DC_PH_R3") (pin "2") (pinfunction "2_2") (pintype "unspecified"))
      (node (ref "DC_PH_T2") (pin "1") (pinfunction "C_1") (pintype "unspecified"))
      (node (ref "DC_PH_ZD2") (pin "2") (pinfunction "2_2") (pintype "unspecified"))
    )
    (net (code "63") (name "Net-(DC_PH_T1-E)") (class "Default")
      (node (ref "DC_PH_R2") (pin "2") (pinfunction "2_2") (pintype "unspecified"))
      (node (ref "DC_PH_T1") (pin "3") (pinfunction "E_3") (pintype "unspecified"))
    )
    (net (code "64") (name "Net-(DC_PH_T2-E)") (class "Default")
      (node (ref "DC_PH_R4") (pin "2") (pinfunction "2_2") (pintype "unspecified"))
      (node (ref "DC_PH_T2") (pin "3") (pinfunction "E_3") (pintype "unspecified"))
    )
    (net (code "65") (name "Net-(DC_R1-Pad3)") (class "Default")
      (node (ref "DC_R1") (pin "3") (pinfunction "3_3") (pintype "unspecified"))
      (node (ref "DC_R1") (pin "4") (pinfunction "4_4") (pintype "unspecified"))
    )
    (net (code "66") (name "Net-(DC_R1-Pad5)") (class "Default")
      (node (ref "DC_R1") (pin "5") (pinfunction "5_5") (pintype "unspecified"))
      (node (ref "H4") (pin "1") (pinfunction "1_1") (pintype "unspecified"))
    )
    (net (code "67") (name "Net-(DC_R1-Pad6)") (class "Default")
      (node (ref "DC_R1") (pin "6") (pinfunction "6_6") (pintype "unspecified"))
      (node (ref "H4") (pin "3") (pinfunction "3_3") (pintype "unspecified"))
    )
    (net (code "68") (name "Net-(DC_R1-Pad7)") (class "Default")
      (node (ref "DC_R1") (pin "7") (pinfunction "7_7") (pintype "unspecified"))
      (node (ref "H4") (pin "5") (pinfunction "5_5") (pintype "unspecified"))
    )
    (net (code "69") (name "Net-(DC_S1-S)") (class "Default")
      (node (ref "DC_S1") (pin "3") (pinfunction "S_3") (pintype "unspecified"))
      (node (ref "DC_S_R1") (pin "1") (pinfunction "1_1") (pintype "unspecified"))
    )
    (net (code "70") (name "Net-(DET_L1-Pad3)") (class "Default")
      (node (ref "DET_L1") (pin "3") (pinfunction "3_3") (pintype "unspecified"))
      (node (ref "DET_M1") (pin "4") (pinfunction "4_4") (pintype "unspecified"))
    )
    (net (code "71") (name "Net-(DET_L1-Pad4)") (class "Default")
      (node (ref "DET_L1") (pin "4") (pinfunction "4_4") (pintype "unspecified"))
      (node (ref "DET_M1") (pin "3") (pinfunction "3_3") (pintype "unspecified"))
    )
    (net (code "72") (name "Net-(DET_L1-Pad5)") (class "Default")
      (node (ref "DET_L1") (pin "5") (pinfunction "5_5") (pintype "unspecified"))
      (node (ref "DET_M1") (pin "2") (pinfunction "2_2") (pintype "unspecified"))
    )
    (net (code "73") (name "Net-(DET_L1-Pad6)") (class "Default")
      (node (ref "DET_L1") (pin "6") (pinfunction "6_6") (pintype "unspecified"))
      (node (ref "DET_M1") (pin "1") (pinfunction "1_1") (pintype "unspecified"))
    )
    (net (code "74") (name "Net-(DET_R1-Pad3)") (class "Default")
      (node (ref "DET_R1") (pin "3") (pinfunction "3_3") (pintype "unspecified"))
      (node (ref "DET_R1") (pin "4") (pinfunction "4_4") (pintype "unspecified"))
    )
    (net (code "75") (name "Net-(DET_R1-Pad5)") (class "Default")
      (node (ref "DET_R1") (pin "5") (pinfunction "5_5") (pintype "unspecified"))
      (node (ref "H18") (pin "1") (pinfunction "1_1") (pintype "unspecified"))
    )
    (net (code "76") (name "Net-(DET_R1-Pad6)") (class "Default")
      (node (ref "DET_R1") (pin "6") (pinfunction "6_6") (pintype "unspecified"))
      (node (ref "H18") (pin "3") (pinfunction "3_3") (pintype "unspecified"))
    )
    (net (code "77") (name "Net-(DET_R1-Pad7)") (class "Default")
      (node (ref "DET_R1") (pin "7") (pinfunction "7_7") (pintype "unspecified"))
      (node (ref "H18") (pin "5") (pinfunction "5_5") (pintype "unspecified"))
    )
    (net (code "78") (name "Net-(DG_L1-Pad3)") (class "Default")
      (node (ref "DG_L1") (pin "3") (pinfunction "3_3") (pintype "unspecified"))
      (node (ref "DG_M2") (pin "4") (pinfunction "4_4") (pintype "unspecified"))
    )
    (net (code "79") (name "Net-(DG_L1-Pad4)") (class "Default")
      (node (ref "DG_L1") (pin "4") (pinfunction "4_4") (pintype "unspecified"))
      (node (ref "DG_M2") (pin "3") (pinfunction "3_3") (pintype "unspecified"))
    )
    (net (code "80") (name "Net-(DG_L1-Pad5)") (class "Default")
      (node (ref "DG_L1") (pin "5") (pinfunction "5_5") (pintype "unspecified"))
      (node (ref "DG_M2") (pin "2") (pinfunction "2_2") (pintype "unspecified"))
    )
    (net (code "81") (name "Net-(DG_L1-Pad6)") (class "Default")
      (node (ref "DG_L1") (pin "6") (pinfunction "6_6") (pintype "unspecified"))
      (node (ref "DG_M2") (pin "1") (pinfunction "1_1") (pintype "unspecified"))
    )
    (net (code "82") (name "Net-(DG_PH_D1-K)") (class "Default")
      (node (ref "DG_PH_C1") (pin "1") (pinfunction "1_1") (pintype "input"))
      (node (ref "DG_PH_C2") (pin "1") (pinfunction "1_1") (pintype "unspecified"))
      (node (ref "DG_PH_C3") (pin "2") (pinfunction "2_2") (pintype "input"))
      (node (ref "DG_PH_C4") (pin "2") (pinfunction "2_2") (pintype "unspecified"))
      (node (ref "DG_PH_D1") (pin "1") (pinfunction "K_1") (pintype "unspecified"))
      (node (ref "DG_PH_M1") (pin "3") (pinfunction "S_3") (pintype "unspecified"))
      (node (ref "DG_PH_R1") (pin "1") (pinfunction "1_1") (pintype "unspecified"))
      (node (ref "DG_PH_ZD1") (pin "1") (pinfunction "1_1") (pintype "unspecified"))
    )
    (net (code "83") (name "Net-(DG_PH_D2-K)") (class "Default")
      (node (ref "DG_PH_C5") (pin "1") (pinfunction "1_1") (pintype "input"))
      (node (ref "DG_PH_D2") (pin "1") (pinfunction "K_1") (pintype "unspecified"))
      (node (ref "DG_PH_M2") (pin "3") (pinfunction "S_3") (pintype "unspecified"))
      (node (ref "DG_PH_R3") (pin "1") (pinfunction "1_1") (pintype "unspecified"))
      (node (ref "DG_PH_ZD2") (pin "1") (pinfunction "1_1") (pintype "unspecified"))
    )
    (net (code "84") (name "Net-(DG_PH_M1-G)") (class "Default")
      (node (ref "DG_PH_M1") (pin "1") (pinfunction "G_1") (pintype "unspecified"))
      (node (ref "DG_PH_R1") (pin "2") (pinfunction "2_2") (pintype "unspecified"))
      (node (ref "DG_PH_T1") (pin "1") (pinfunction "C_1") (pintype "unspecified"))
      (node (ref "DG_PH_ZD1") (pin "2") (pinfunction "2_2") (pintype "unspecified"))
    )
    (net (code "85") (name "Net-(DG_PH_M2-G)") (class "Default")
      (node (ref "DG_PH_M2") (pin "1") (pinfunction "G_1") (pintype "unspecified"))
      (node (ref "DG_PH_R3") (pin "2") (pinfunction "2_2") (pintype "unspecified"))
      (node (ref "DG_PH_T2") (pin "1") (pinfunction "C_1") (pintype "unspecified"))
      (node (ref "DG_PH_ZD2") (pin "2") (pinfunction "2_2") (pintype "unspecified"))
    )
    (net (code "86") (name "Net-(DG_PH_T1-E)") (class "Default")
      (node (ref "DG_PH_R2") (pin "2") (pinfunction "2_2") (pintype "unspecified"))
      (node (ref "DG_PH_T1") (pin "3") (pinfunction "E_3") (pintype "unspecified"))
    )
    (net (code "87") (name "Net-(DG_PH_T2-E)") (class "Default")
      (node (ref "DG_PH_R4") (pin "2") (pinfunction "2_2") (pintype "unspecified"))
      (node (ref "DG_PH_T2") (pin "3") (pinfunction "E_3") (pintype "unspecified"))
    )
    (net (code "88") (name "Net-(DG_R1-Pad3)") (class "Default")
      (node (ref "DG_R1") (pin "3") (pinfunction "3_3") (pintype "unspecified"))
      (node (ref "DG_R1") (pin "4") (pinfunction "4_4") (pintype "unspecified"))
    )
    (net (code "89") (name "Net-(DG_R1-Pad5)") (class "Default")
      (node (ref "DG_R1") (pin "5") (pinfunction "5_5") (pintype "unspecified"))
      (node (ref "H3") (pin "1") (pinfunction "1_1") (pintype "unspecified"))
    )
    (net (code "90") (name "Net-(DG_R1-Pad6)") (class "Default")
      (node (ref "DG_R1") (pin "6") (pinfunction "6_6") (pintype "unspecified"))
      (node (ref "H3") (pin "3") (pinfunction "3_3") (pintype "unspecified"))
    )
    (net (code "91") (name "Net-(DG_R1-Pad7)") (class "Default")
      (node (ref "DG_R1") (pin "7") (pinfunction "7_7") (pintype "unspecified"))
      (node (ref "H3") (pin "5") (pinfunction "5_5") (pintype "unspecified"))
    )
    (net (code "92") (name "Net-(DG_S1-S)") (class "Default")
      (node (ref "DG_S1") (pin "3") (pinfunction "S_3") (pintype "unspecified"))
      (node (ref "DG_S_R1") (pin "1") (pinfunction "1_1") (pintype "unspecified"))
    )
    (net (code "93") (name "Net-(DT_L1-Pad3)") (class "Default")
      (node (ref "DT_L1") (pin "3") (pinfunction "3_3") (pintype "unspecified"))
      (node (ref "DT_M2") (pin "4") (pinfunction "4_4") (pintype "unspecified"))
    )
    (net (code "94") (name "Net-(DT_L1-Pad4)") (class "Default")
      (node (ref "DT_L1") (pin "4") (pinfunction "4_4") (pintype "unspecified"))
      (node (ref "DT_M2") (pin "3") (pinfunction "3_3") (pintype "unspecified"))
    )
    (net (code "95") (name "Net-(DT_L1-Pad5)") (class "Default")
      (node (ref "DT_L1") (pin "5") (pinfunction "5_5") (pintype "unspecified"))
      (node (ref "DT_M2") (pin "2") (pinfunction "2_2") (pintype "unspecified"))
    )
    (net (code "96") (name "Net-(DT_L1-Pad6)") (class "Default")
      (node (ref "DT_L1") (pin "6") (pinfunction "6_6") (pintype "unspecified"))
      (node (ref "DT_M2") (pin "1") (pinfunction "1_1") (pintype "unspecified"))
    )
    (net (code "97") (name "Net-(DT_PH_D1-K)") (class "Default")
      (node (ref "DT_PH_C1") (pin "1") (pinfunction "1_1") (pintype "input"))
      (node (ref "DT_PH_C2") (pin "1") (pinfunction "1_1") (pintype "unspecified"))
      (node (ref "DT_PH_C3") (pin "2") (pinfunction "2_2") (pintype "input"))
      (node (ref "DT_PH_C4") (pin "2") (pinfunction "2_2") (pintype "unspecified"))
      (node (ref "DT_PH_D1") (pin "1") (pinfunction "K_1") (pintype "unspecified"))
      (node (ref "DT_PH_M1") (pin "3") (pinfunction "S_3") (pintype "unspecified"))
      (node (ref "DT_PH_R1") (pin "1") (pinfunction "1_1") (pintype "unspecified"))
      (node (ref "DT_PH_ZD1") (pin "1") (pinfunction "1_1") (pintype "unspecified"))
    )
    (net (code "98") (name "Net-(DT_PH_D2-K)") (class "Default")
      (node (ref "DT_PH_C5") (pin "1") (pinfunction "1_1") (pintype "input"))
      (node (ref "DT_PH_D2") (pin "1") (pinfunction "K_1") (pintype "unspecified"))
      (node (ref "DT_PH_M2") (pin "3") (pinfunction "S_3") (pintype "unspecified"))
      (node (ref "DT_PH_R3") (pin "1") (pinfunction "1_1") (pintype "unspecified"))
      (node (ref "DT_PH_ZD2") (pin "1") (pinfunction "1_1") (pintype "unspecified"))
    )
    (net (code "99") (name "Net-(DT_PH_M1-G)") (class "Default")
      (node (ref "DT_PH_M1") (pin "1") (pinfunction "G_1") (pintype "unspecified"))
      (node (ref "DT_PH_R1") (pin "2") (pinfunction "2_2") (pintype "unspecified"))
      (node (ref "DT_PH_T1") (pin "1") (pinfunction "C_1") (pintype "unspecified"))
      (node (ref "DT_PH_ZD1") (pin "2") (pinfunction "2_2") (pintype "unspecified"))
    )
    (net (code "100") (name "Net-(DT_PH_M2-G)") (class "Default")
      (node (ref "DT_PH_M2") (pin "1") (pinfunction "G_1") (pintype "unspecified"))
      (node (ref "DT_PH_R3") (pin "2") (pinfunction "2_2") (pintype "unspecified"))
      (node (ref "DT_PH_T2") (pin "1") (pinfunction "C_1") (pintype "unspecified"))
      (node (ref "DT_PH_ZD2") (pin "2") (pinfunction "2_2") (pintype "unspecified"))
    )
    (net (code "101") (name "Net-(DT_PH_T1-E)") (class "Default")
      (node (ref "DT_PH_R2") (pin "2") (pinfunction "2_2") (pintype "unspecified"))
      (node (ref "DT_PH_T1") (pin "3") (pinfunction "E_3") (pintype "unspecified"))
    )
    (net (code "102") (name "Net-(DT_PH_T2-E)") (class "Default")
      (node (ref "DT_PH_R4") (pin "2") (pinfunction "2_2") (pintype "unspecified"))
      (node (ref "DT_PH_T2") (pin "3") (pinfunction "E_3") (pintype "unspecified"))
    )
    (net (code "103") (name "Net-(DT_R1-Pad3)") (class "Default")
      (node (ref "DT_R1") (pin "3") (pinfunction "3_3") (pintype "unspecified"))
      (node (ref "DT_R1") (pin "4") (pinfunction "4_4") (pintype "unspecified"))
    )
    (net (code "104") (name "Net-(DT_R1-Pad5)") (class "Default")
      (node (ref "DT_R1") (pin "5") (pinfunction "5_5") (pintype "unspecified"))
      (node (ref "H2") (pin "1") (pinfunction "1_1") (pintype "unspecified"))
    )
    (net (code "105") (name "Net-(DT_R1-Pad6)") (class "Default")
      (node (ref "DT_R1") (pin "6") (pinfunction "6_6") (pintype "unspecified"))
      (node (ref "H2") (pin "3") (pinfunction "3_3") (pintype "unspecified"))
    )
    (net (code "106") (name "Net-(DT_R1-Pad7)") (class "Default")
      (node (ref "DT_R1") (pin "7") (pinfunction "7_7") (pintype "unspecified"))
      (node (ref "H2") (pin "5") (pinfunction "5_5") (pintype "unspecified"))
    )
    (net (code "107") (name "Net-(DT_S1-S)") (class "Default")
      (node (ref "DT_S1") (pin "3") (pinfunction "S_3") (pintype "unspecified"))
      (node (ref "DT_S_R1") (pin "1") (pinfunction "1_1") (pintype "unspecified"))
    )
    (net (code "108") (name "Net-(H8-5V)") (class "Default")
      (node (ref "H8") (pin "5") (pinfunction "5V_5") (pintype "unspecified"))
      (node (ref "R2") (pin "1") (pinfunction "1_1") (pintype "unspecified"))
      (node (ref "SW1") (pin "3") (pinfunction "3_3") (pintype "unspecified"))
    )
    (net (code "109") (name "Net-(H8-RESET)") (class "Default")
      (node (ref "H8") (pin "3") (pinfunction "RESET_3") (pintype "unspecified"))
      (node (ref "SW1") (pin "1") (pinfunction "1_1") (pintype "unspecified"))
    )
    (net (code "110") (name "Net-(H14-Pad1)") (class "Default")
      (node (ref "H14") (pin "1") (pinfunction "1_1") (pintype "unspecified"))
      (node (ref "WASH_R1") (pin "5") (pinfunction "5_5") (pintype "unspecified"))
    )
    (net (code "111") (name "Net-(H14-Pad3)") (class "Default")
      (node (ref "H14") (pin "3") (pinfunction "3_3") (pintype "unspecified"))
      (node (ref "WASH_R1") (pin "6") (pinfunction "6_6") (pintype "unspecified"))
    )
    (net (code "112") (name "Net-(H14-Pad5)") (class "Default")
      (node (ref "H14") (pin "5") (pinfunction "5_5") (pintype "unspecified"))
      (node (ref "WASH_R1") (pin "7") (pinfunction "7_7") (pintype "unspecified"))
    )
    (net (code "113") (name "Net-(H15-Pad1)") (class "Default")
      (node (ref "H15") (pin "1") (pinfunction "1_1") (pintype "unspecified"))
      (node (ref "WASTE2_R") (pin "5") (pinfunction "5_5") (pintype "unspecified"))
    )
    (net (code "114") (name "Net-(H15-Pad3)") (class "Default")
      (node (ref "H15") (pin "3") (pinfunction "3_3") (pintype "unspecified"))
      (node (ref "WASTE2_R") (pin "6") (pinfunction "6_6") (pintype "unspecified"))
    )
    (net (code "115") (name "Net-(H15-Pad5)") (class "Default")
      (node (ref "H15") (pin "5") (pinfunction "5_5") (pintype "unspecified"))
      (node (ref "WASTE2_R") (pin "7") (pinfunction "7_7") (pintype "unspecified"))
    )
    (net (code "116") (name "Net-(H16-Pad1)") (class "Default")
      (node (ref "H16") (pin "1") (pinfunction "1_1") (pintype "unspecified"))
      (node (ref "WASTE1_R") (pin "5") (pinfunction "5_5") (pintype "unspecified"))
    )
    (net (code "117") (name "Net-(H16-Pad3)") (class "Default")
      (node (ref "H16") (pin "3") (pinfunction "3_3") (pintype "unspecified"))
      (node (ref "WASTE1_R") (pin "6") (pinfunction "6_6") (pintype "unspecified"))
    )
    (net (code "118") (name "Net-(H16-Pad5)") (class "Default")
      (node (ref "H16") (pin "5") (pinfunction "5_5") (pintype "unspecified"))
      (node (ref "WASTE1_R") (pin "7") (pinfunction "7_7") (pintype "unspecified"))
    )
    (net (code "119") (name "Net-(H17-Pad1)") (class "Default")
      (node (ref "H17") (pin "1") (pinfunction "1_1") (pintype "unspecified"))
      (node (ref "OXI_R1") (pin "5") (pinfunction "5_5") (pintype "unspecified"))
    )
    (net (code "120") (name "Net-(H17-Pad3)") (class "Default")
      (node (ref "H17") (pin "3") (pinfunction "3_3") (pintype "unspecified"))
      (node (ref "OXI_R1") (pin "6") (pinfunction "6_6") (pintype "unspecified"))
    )
    (net (code "121") (name "Net-(H17-Pad5)") (class "Default")
      (node (ref "H17") (pin "5") (pinfunction "5_5") (pintype "unspecified"))
      (node (ref "OXI_R1") (pin "7") (pinfunction "7_7") (pintype "unspecified"))
    )
    (net (code "122") (name "Net-(H19-Pad1)") (class "Default")
      (node (ref "H19") (pin "1") (pinfunction "1_1") (pintype "unspecified"))
      (node (ref "LINEAR_R1") (pin "5") (pinfunction "5_5") (pintype "unspecified"))
    )
    (net (code "123") (name "Net-(H19-Pad3)") (class "Default")
      (node (ref "H19") (pin "3") (pinfunction "3_3") (pintype "unspecified"))
      (node (ref "LINEAR_R1") (pin "6") (pinfunction "6_6") (pintype "unspecified"))
    )
    (net (code "124") (name "Net-(H19-Pad5)") (class "Default")
      (node (ref "H19") (pin "5") (pinfunction "5_5") (pintype "unspecified"))
      (node (ref "LINEAR_R1") (pin "7") (pinfunction "7_7") (pintype "unspecified"))
    )
    (net (code "125") (name "Net-(LINEAR_L1-Pad3)") (class "Default")
      (node (ref "LINEAR_L1") (pin "3") (pinfunction "3_3") (pintype "unspecified"))
      (node (ref "LINEAR_M1") (pin "4") (pinfunction "4_4") (pintype "unspecified"))
    )
    (net (code "126") (name "Net-(LINEAR_L1-Pad4)") (class "Default")
      (node (ref "LINEAR_L1") (pin "4") (pinfunction "4_4") (pintype "unspecified"))
      (node (ref "LINEAR_M1") (pin "3") (pinfunction "3_3") (pintype "unspecified"))
    )
    (net (code "127") (name "Net-(LINEAR_L1-Pad5)") (class "Default")
      (node (ref "LINEAR_L1") (pin "5") (pinfunction "5_5") (pintype "unspecified"))
      (node (ref "LINEAR_M1") (pin "2") (pinfunction "2_2") (pintype "unspecified"))
    )
    (net (code "128") (name "Net-(LINEAR_L1-Pad6)") (class "Default")
      (node (ref "LINEAR_L1") (pin "6") (pinfunction "6_6") (pintype "unspecified"))
      (node (ref "LINEAR_M1") (pin "1") (pinfunction "1_1") (pintype "unspecified"))
    )
    (net (code "129") (name "Net-(LINEAR_R1-Pad3)") (class "Default")
      (node (ref "LINEAR_R1") (pin "3") (pinfunction "3_3") (pintype "unspecified"))
      (node (ref "LINEAR_R1") (pin "4") (pinfunction "4_4") (pintype "unspecified"))
    )
    (net (code "130") (name "Net-(MEGA-IOREF1-5V)") (class "Default")
      (node (ref "MEGA-IOREF1") (pin "5") (pinfunction "5V_5") (pintype "unspecified"))
      (node (ref "SW3") (pin "2") (pinfunction "2_2") (pintype "unspecified"))
    )
    (net (code "131") (name "Net-(MEGA-IOREF1-RESET)") (class "Default")
      (node (ref "MEGA-IOREF1") (pin "3") (pinfunction "RESET_3") (pintype "unspecified"))
      (node (ref "SW3") (pin "4") (pinfunction "4_4") (pintype "unspecified"))
    )
    (net (code "132") (name "Net-(OXI_L1-Pad3)") (class "Default")
      (node (ref "OXI_L1") (pin "3") (pinfunction "3_3") (pintype "unspecified"))
      (node (ref "OXI_M1") (pin "4") (pinfunction "4_4") (pintype "unspecified"))
    )
    (net (code "133") (name "Net-(OXI_L1-Pad4)") (class "Default")
      (node (ref "OXI_L1") (pin "4") (pinfunction "4_4") (pintype "unspecified"))
      (node (ref "OXI_M1") (pin "3") (pinfunction "3_3") (pintype "unspecified"))
    )
    (net (code "134") (name "Net-(OXI_L1-Pad5)") (class "Default")
      (node (ref "OXI_L1") (pin "5") (pinfunction "5_5") (pintype "unspecified"))
      (node (ref "OXI_M1") (pin "2") (pinfunction "2_2") (pintype "unspecified"))
    )
    (net (code "135") (name "Net-(OXI_L1-Pad6)") (class "Default")
      (node (ref "OXI_L1") (pin "6") (pinfunction "6_6") (pintype "unspecified"))
      (node (ref "OXI_M1") (pin "1") (pinfunction "1_1") (pintype "unspecified"))
    )
    (net (code "136") (name "Net-(OXI_R1-Pad3)") (class "Default")
      (node (ref "OXI_R1") (pin "3") (pinfunction "3_3") (pintype "unspecified"))
      (node (ref "OXI_R1") (pin "4") (pinfunction "4_4") (pintype "unspecified"))
    )
    (net (code "137") (name "Net-(Q2-B)") (class "Default")
      (node (ref "Q2") (pin "1") (pinfunction "B_1") (pintype "input"))
      (node (ref "R6") (pin "1") (pinfunction "1_1") (pintype "unspecified"))
    )
    (net (code "138") (name "Net-(Q2-C)") (class "Default")
      (node (ref "D2") (pin "2") (pinfunction "2_2") (pintype "unspecified"))
      (node (ref "Q2") (pin "2") (pinfunction "C_2") (pintype "input"))
      (node (ref "U6") (pin "2") (pinfunction "GND_2") (pintype "unspecified"))
    )
    (net (code "139") (name "Net-(U5-none)") (class "Default")
      (node (ref "R1") (pin "2") (pinfunction "2_2") (pintype "unspecified"))
      (node (ref "U5") (pin "1") (pinfunction "none_1") (pintype "unspecified"))
    )
    (net (code "140") (name "Net-(WASH_L1-A1)") (class "Default")
      (node (ref "WASH_L1") (pin "4") (pinfunction "A1_4") (pintype "unspecified"))
      (node (ref "WASH_M1") (pin "3") (pinfunction "3_3") (pintype "unspecified"))
    )
    (net (code "141") (name "Net-(WASH_L1-A2)") (class "Default")
      (node (ref "WASH_L1") (pin "5") (pinfunction "A2_5") (pintype "unspecified"))
      (node (ref "WASH_M1") (pin "2") (pinfunction "2_2") (pintype "unspecified"))
    )
    (net (code "142") (name "Net-(WASH_L1-B1)") (class "Default")
      (node (ref "WASH_L1") (pin "3") (pinfunction "B1_3") (pintype "unspecified"))
      (node (ref "WASH_M1") (pin "4") (pinfunction "4_4") (pintype "unspecified"))
    )
    (net (code "143") (name "Net-(WASH_L1-B2)") (class "Default")
      (node (ref "WASH_L1") (pin "6") (pinfunction "B2_6") (pintype "unspecified"))
      (node (ref "WASH_M1") (pin "1") (pinfunction "1_1") (pintype "unspecified"))
    )
    (net (code "144") (name "Net-(WASH_R1-Pad3)") (class "Default")
      (node (ref "WASH_R1") (pin "3") (pinfunction "3_3") (pintype "unspecified"))
      (node (ref "WASH_R1") (pin "4") (pinfunction "4_4") (pintype "unspecified"))
    )
    (net (code "145") (name "Net-(WASTE1_L-Pad3)") (class "Default")
      (node (ref "WASTE1_L") (pin "3") (pinfunction "3_3") (pintype "unspecified"))
      (node (ref "WASTE1_M") (pin "4") (pinfunction "4_4") (pintype "unspecified"))
    )
    (net (code "146") (name "Net-(WASTE1_L-Pad4)") (class "Default")
      (node (ref "WASTE1_L") (pin "4") (pinfunction "4_4") (pintype "unspecified"))
      (node (ref "WASTE1_M") (pin "3") (pinfunction "3_3") (pintype "unspecified"))
    )
    (net (code "147") (name "Net-(WASTE1_L-Pad5)") (class "Default")
      (node (ref "WASTE1_L") (pin "5") (pinfunction "5_5") (pintype "unspecified"))
      (node (ref "WASTE1_M") (pin "2") (pinfunction "2_2") (pintype "unspecified"))
    )
    (net (code "148") (name "Net-(WASTE1_L-Pad6)") (class "Default")
      (node (ref "WASTE1_L") (pin "6") (pinfunction "6_6") (pintype "unspecified"))
      (node (ref "WASTE1_M") (pin "1") (pinfunction "1_1") (pintype "unspecified"))
    )
    (net (code "149") (name "Net-(WASTE1_R-Pad3)") (class "Default")
      (node (ref "WASTE1_R") (pin "3") (pinfunction "3_3") (pintype "unspecified"))
      (node (ref "WASTE1_R") (pin "4") (pinfunction "4_4") (pintype "unspecified"))
    )
    (net (code "150") (name "Net-(WASTE2_L-Pad3)") (class "Default")
      (node (ref "WASTE2_L") (pin "3") (pinfunction "3_3") (pintype "unspecified"))
      (node (ref "WASTE2_M") (pin "4") (pinfunction "4_4") (pintype "unspecified"))
    )
    (net (code "151") (name "Net-(WASTE2_L-Pad4)") (class "Default")
      (node (ref "WASTE2_L") (pin "4") (pinfunction "4_4") (pintype "unspecified"))
      (node (ref "WASTE2_M") (pin "3") (pinfunction "3_3") (pintype "unspecified"))
    )
    (net (code "152") (name "Net-(WASTE2_L-Pad5)") (class "Default")
      (node (ref "WASTE2_L") (pin "5") (pinfunction "5_5") (pintype "unspecified"))
      (node (ref "WASTE2_M") (pin "2") (pinfunction "2_2") (pintype "unspecified"))
    )
    (net (code "153") (name "Net-(WASTE2_L-Pad6)") (class "Default")
      (node (ref "WASTE2_L") (pin "6") (pinfunction "6_6") (pintype "unspecified"))
      (node (ref "WASTE2_M") (pin "1") (pinfunction "1_1") (pintype "unspecified"))
    )
    (net (code "154") (name "Net-(WASTE2_R-Pad3)") (class "Default")
      (node (ref "WASTE2_R") (pin "3") (pinfunction "3_3") (pintype "unspecified"))
      (node (ref "WASTE2_R") (pin "4") (pinfunction "4_4") (pintype "unspecified"))
    )
    (net (code "155") (name "OXI_E") (class "Default")
      (node (ref "MEGA-SCL2") (pin "10") (pinfunction "8_10") (pintype "unspecified"))
    )
    (net (code "156") (name "OXI_enable") (class "Default")
      (node (ref "OXI_R1") (pin "8") (pinfunction "8_8") (pintype "unspecified"))
    )
    (net (code "157") (name "OXI_pulse") (class "Default")
      (node (ref "MEGA-D1") (pin "6") (pinfunction "2_6") (pintype "unspecified"))
    )
    (net (code "158") (name "OXI_step") (class "Default")
      (node (ref "OXI_R1") (pin "2") (pinfunction "2_2") (pintype "unspecified"))
    )
    (net (code "159") (name "PH_35V") (class "Default")
      (node (ref "ACT_PH_D1") (pin "2") (pinfunction "A_2") (pintype "unspecified"))
      (node (ref "ACT_PH_D2") (pin "2") (pinfunction "A_2") (pintype "unspecified"))
      (node (ref "DA_PH_D1") (pin "2") (pinfunction "A_2") (pintype "unspecified"))
      (node (ref "DA_PH_D2") (pin "2") (pinfunction "A_2") (pintype "unspecified"))
      (node (ref "DC_PH_D1") (pin "2") (pinfunction "A_2") (pintype "unspecified"))
      (node (ref "DC_PH_D2") (pin "2") (pinfunction "A_2") (pintype "unspecified"))
      (node (ref "DG_PH_D1") (pin "2") (pinfunction "A_2") (pintype "unspecified"))
      (node (ref "DG_PH_D2") (pin "2") (pinfunction "A_2") (pintype "unspecified"))
      (node (ref "DT_PH_D1") (pin "2") (pinfunction "A_2") (pintype "unspecified"))
      (node (ref "DT_PH_D2") (pin "2") (pinfunction "A_2") (pintype "unspecified"))
    )
    (net (code "160") (name "PH_CLK") (class "Default")
      (node (ref "ACT_PRINTHEAD1") (pin "15") (pinfunction "CLK_15") (pintype "unspecified"))
      (node (ref "DA_PRINTHEAD1") (pin "15") (pinfunction "CLK_15") (pintype "unspecified"))
      (node (ref "DC_PRINTHEAD1") (pin "15") (pinfunction "CLK_15") (pintype "unspecified"))
      (node (ref "DG_PRINTHEAD1") (pin "15") (pinfunction "CLK_15") (pintype "unspecified"))
      (node (ref "DT_PRINTHEAD1") (pin "15") (pinfunction "CLK_15") (pintype "unspecified"))
      (node (ref "U5") (pin "16") (pinfunction "50_16") (pintype "unspecified"))
    )
    (net (code "161") (name "PH_MISO") (class "Default")
      (node (ref "ACT_PRINTHEAD1") (pin "13") (pinfunction "MISO_13") (pintype "unspecified"))
      (node (ref "DA_PRINTHEAD1") (pin "13") (pinfunction "MISO_13") (pintype "unspecified"))
      (node (ref "DC_PRINTHEAD1") (pin "13") (pinfunction "MISO_13") (pintype "unspecified"))
      (node (ref "DG_PRINTHEAD1") (pin "13") (pinfunction "MISO_13") (pintype "unspecified"))
      (node (ref "DT_PRINTHEAD1") (pin "13") (pinfunction "MISO_13") (pintype "unspecified"))
      (node (ref "U5") (pin "15") (pinfunction "48_15") (pintype "unspecified"))
    )
    (net (code "162") (name "PH_MOSI") (class "Default")
      (node (ref "ACT_PRINTHEAD1") (pin "8") (pinfunction "MOSI_8") (pintype "unspecified"))
      (node (ref "DA_PRINTHEAD1") (pin "8") (pinfunction "MOSI_8") (pintype "unspecified"))
      (node (ref "DC_PRINTHEAD1") (pin "8") (pinfunction "MOSI_8") (pintype "unspecified"))
      (node (ref "DG_PRINTHEAD1") (pin "8") (pinfunction "MOSI_8") (pintype "unspecified"))
      (node (ref "DT_PRINTHEAD1") (pin "8") (pinfunction "MOSI_8") (pintype "unspecified"))
      (node (ref "U7") (pin "4") (pinfunction "49_4") (pintype "unspecified"))
    )
    (net (code "163") (name "PH_SCK") (class "Default")
      (node (ref "ACT_PRINTHEAD1") (pin "11") (pinfunction "SCK_11") (pintype "unspecified"))
      (node (ref "DA_PRINTHEAD1") (pin "11") (pinfunction "SCK_11") (pintype "unspecified"))
      (node (ref "DC_PRINTHEAD1") (pin "11") (pinfunction "SCK_11") (pintype "unspecified"))
      (node (ref "DG_PRINTHEAD1") (pin "11") (pinfunction "SCK_11") (pintype "unspecified"))
      (node (ref "DT_PRINTHEAD1") (pin "11") (pinfunction "SCK_11") (pintype "unspecified"))
      (node (ref "U7") (pin "5") (pinfunction "47_5") (pintype "unspecified"))
    )
    (net (code "164") (name "PH_reset") (class "Default")
      (node (ref "ACT_PRINTHEAD1") (pin "7") (pinfunction "RESET_7") (pintype "unspecified"))
      (node (ref "DA_PRINTHEAD1") (pin "7") (pinfunction "RESET_7") (pintype "unspecified"))
      (node (ref "DC_PRINTHEAD1") (pin "7") (pinfunction "RESET_7") (pintype "unspecified"))
      (node (ref "DG_PRINTHEAD1") (pin "7") (pinfunction "RESET_7") (pintype "unspecified"))
      (node (ref "DT_PRINTHEAD1") (pin "7") (pinfunction "RESET_7") (pintype "unspecified"))
      (node (ref "U7") (pin "3") (pinfunction "51_3") (pintype "unspecified"))
    )
    (net (code "165") (name "RX") (class "Default")
      (node (ref "MEGA-D1") (pin "8") (pinfunction "0_8") (pintype "unspecified"))
    )
    (net (code "166") (name "SCL") (class "Default")
      (node (ref "H9") (pin "6") (pinfunction "A5_6") (pintype "input"))
      (node (ref "MEGA-D2") (pin "8") (pinfunction "21_8") (pintype "unspecified"))
    )
    (net (code "167") (name "SDA") (class "Default")
      (node (ref "H9") (pin "5") (pinfunction "A4_5") (pintype "input"))
      (node (ref "MEGA-D2") (pin "7") (pinfunction "20_7") (pintype "unspecified"))
    )
    (net (code "168") (name "TX") (class "Default")
      (node (ref "MEGA-D1") (pin "7") (pinfunction "1_7") (pintype "unspecified"))
    )
    (net (code "169") (name "bulk_RX") (class "Default")
      (node (ref "MEGA-D2") (pin "6") (pinfunction "19_6") (pintype "unspecified"))
    )
    (net (code "170") (name "bulk_TX") (class "Default")
      (node (ref "MEGA-D2") (pin "5") (pinfunction "18_5") (pintype "unspecified"))
    )
    (net (code "171") (name "bulk_direction") (class "Default")
      (node (ref "DET_R1") (pin "1") (pinfunction "1_1") (pintype "unspecified"))
      (node (ref "OXI_R1") (pin "1") (pinfunction "1_1") (pintype "unspecified"))
      (node (ref "WASH_R1") (pin "1") (pinfunction "1_1") (pintype "unspecified"))
    )
    (net (code "172") (name "dA_PH_VPPH") (class "Default")
      (node (ref "DA_PH_M2") (pin "2") (pinfunction "D_2") (pintype "unspecified"))
      (node (ref "DA_PRINTHEAD1") (pin "3") (pinfunction "VPPH_3") (pintype "unspecified"))
    )
    (net (code "173") (name "dA_PH_VPPL") (class "Default")
      (node (ref "DA_PH_M1") (pin "2") (pinfunction "D_2") (pintype "unspecified"))
      (node (ref "DA_PRINTHEAD1") (pin "4") (pinfunction "VPPL_4") (pintype "unspecified"))
    )
    (net (code "174") (name "dA_PH_fault") (class "Default")
      (node (ref "DA_PRINTHEAD1") (pin "6") (pinfunction "FAULT_6") (pintype "unspecified"))
      (node (ref "U7") (pin "14") (pinfunction "29_14") (pintype "unspecified"))
    )
    (net (code "175") (name "dA_PH_fire") (class "Default")
      (node (ref "DA_PRINTHEAD1") (pin "16") (pinfunction "FIRE_16") (pintype "unspecified"))
      (node (ref "U5") (pin "6") (pinfunction "30_6") (pintype "unspecified"))
    )
    (net (code "176") (name "dA_PH_nSS1") (class "Default")
      (node (ref "DA_PRINTHEAD1") (pin "12") (pinfunction "nSS1_12") (pintype "unspecified"))
      (node (ref "U7") (pin "15") (pinfunction "27_15") (pintype "unspecified"))
    )
    (net (code "177") (name "dA_PH_nSS2") (class "Default")
      (node (ref "DA_PRINTHEAD1") (pin "1") (pinfunction "nSS2_1") (pintype "unspecified"))
      (node (ref "U5") (pin "5") (pinfunction "28_5") (pintype "unspecified"))
    )
    (net (code "178") (name "dA_PH_ready") (class "Default")
      (node (ref "DA_PRINTHEAD1") (pin "14") (pinfunction "READY_14") (pintype "unspecified"))
      (node (ref "U7") (pin "13") (pinfunction "31_13") (pintype "unspecified"))
    )
    (net (code "179") (name "dA_S") (class "Default")
      (node (ref "DA_S_R1") (pin "2") (pinfunction "2_2") (pintype "unspecified"))
      (node (ref "DA_S_R2") (pin "1") (pinfunction "1_1") (pintype "unspecified"))
      (node (ref "H9") (pin "2") (pinfunction "A1_2") (pintype "input"))
    )
    (net (code "180") (name "dA_enable") (class "Default")
      (node (ref "DA_R1") (pin "8") (pinfunction "8_8") (pintype "unspecified"))
      (node (ref "H7") (pin "7") (pinfunction "1_7") (pintype "unspecified"))
    )
    (net (code "181") (name "dA_step") (class "Default")
      (node (ref "DA_R1") (pin "2") (pinfunction "2_2") (pintype "unspecified"))
      (node (ref "H7") (pin "2") (pinfunction "6_2") (pintype "unspecified"))
    )
    (net (code "182") (name "dC_PH_VPPH") (class "Default")
      (node (ref "DC_PH_M2") (pin "2") (pinfunction "D_2") (pintype "unspecified"))
      (node (ref "DC_PRINTHEAD1") (pin "3") (pinfunction "VPPH_3") (pintype "unspecified"))
    )
    (net (code "183") (name "dC_PH_VPPL") (class "Default")
      (node (ref "DC_PH_M1") (pin "2") (pinfunction "D_2") (pintype "unspecified"))
      (node (ref "DC_PRINTHEAD1") (pin "4") (pinfunction "VPPL_4") (pintype "unspecified"))
    )
    (net (code "184") (name "dC_PH_fault") (class "Default")
      (node (ref "DC_PRINTHEAD1") (pin "6") (pinfunction "FAULT_6") (pintype "unspecified"))
      (node (ref "U5") (pin "13") (pinfunction "44_13") (pintype "unspecified"))
    )
    (net (code "185") (name "dC_PH_fire") (class "Default")
      (node (ref "DC_PRINTHEAD1") (pin "16") (pinfunction "FIRE_16") (pintype "unspecified"))
      (node (ref "U7") (pin "6") (pinfunction "45_6") (pintype "unspecified"))
    )
    (net (code "186") (name "dC_PH_nSS1") (class "Default")
      (node (ref "DC_PRINTHEAD1") (pin "12") (pinfunction "nSS1_12") (pintype "unspecified"))
      (node (ref "U5") (pin "12") (pinfunction "42_12") (pintype "unspecified"))
    )
    (net (code "187") (name "dC_PH_nSS2") (class "Default")
      (node (ref "DC_PRINTHEAD1") (pin "1") (pinfunction "nSS2_1") (pintype "unspecified"))
      (node (ref "U7") (pin "7") (pinfunction "43_7") (pintype "unspecified"))
    )
    (net (code "188") (name "dC_PH_ready") (class "Default")
      (node (ref "DC_PRINTHEAD1") (pin "14") (pinfunction "READY_14") (pintype "unspecified"))
      (node (ref "U5") (pin "14") (pinfunction "46_14") (pintype "unspecified"))
    )
    (net (code "189") (name "dC_S") (class "Default")
      (node (ref "DC_S_R1") (pin "2") (pinfunction "2_2") (pintype "unspecified"))
      (node (ref "DC_S_R2") (pin "1") (pinfunction "1_1") (pintype "unspecified"))
      (node (ref "H6") (pin "7") (pinfunction "11_7") (pintype "unspecified"))
    )
    (net (code "190") (name "dC_enable") (class "Default")
      (node (ref "DC_R1") (pin "8") (pinfunction "8_8") (pintype "unspecified"))
      (node (ref "H7") (pin "4") (pinfunction "4_4") (pintype "unspecified"))
    )
    (net (code "191") (name "dC_step") (class "Default")
      (node (ref "DC_R1") (pin "2") (pinfunction "2_2") (pintype "unspecified"))
      (node (ref "H6") (pin "9") (pinfunction "9_9") (pintype "unspecified"))
    )
    (net (code "192") (name "dG_PH_VPPH") (class "Default")
      (node (ref "DG_PH_M2") (pin "2") (pinfunction "D_2") (pintype "unspecified"))
      (node (ref "DG_PRINTHEAD1") (pin "3") (pinfunction "VPPH_3") (pintype "unspecified"))
    )
    (net (code "193") (name "dG_PH_VPPL") (class "Default")
      (node (ref "DG_PH_M1") (pin "2") (pinfunction "D_2") (pintype "unspecified"))
      (node (ref "DG_PRINTHEAD1") (pin "4") (pinfunction "VPPL_4") (pintype "unspecified"))
    )
    (net (code "194") (name "dG_PH_fault") (class "Default")
      (node (ref "DG_PRINTHEAD1") (pin "6") (pinfunction "FAULT_6") (pintype "unspecified"))
      (node (ref "U7") (pin "9") (pinfunction "39_9") (pintype "unspecified"))
    )
    (net (code "195") (name "dG_PH_fire") (class "Default")
      (node (ref "DG_PRINTHEAD1") (pin "16") (pinfunction "FIRE_16") (pintype "unspecified"))
      (node (ref "U5") (pin "11") (pinfunction "40_11") (pintype "unspecified"))
    )
    (net (code "196") (name "dG_PH_nSS1") (class "Default")
      (node (ref "DG_PRINTHEAD1") (pin "12") (pinfunction "nSS1_12") (pintype "unspecified"))
      (node (ref "U7") (pin "10") (pinfunction "37_10") (pintype "unspecified"))
    )
    (net (code "197") (name "dG_PH_nSS2") (class "Default")
      (node (ref "DG_PRINTHEAD1") (pin "1") (pinfunction "nSS2_1") (pintype "unspecified"))
      (node (ref "U5") (pin "10") (pinfunction "38_10") (pintype "unspecified"))
    )
    (net (code "198") (name "dG_PH_ready") (class "Default")
      (node (ref "DG_PRINTHEAD1") (pin "14") (pinfunction "READY_14") (pintype "unspecified"))
      (node (ref "U7") (pin "8") (pinfunction "41_8") (pintype "unspecified"))
    )
    (net (code "199") (name "dG_S") (class "Default")
      (node (ref "DG_S_R1") (pin "2") (pinfunction "2_2") (pintype "unspecified"))
      (node (ref "DG_S_R2") (pin "1") (pinfunction "1_1") (pintype "unspecified"))
      (node (ref "H9") (pin "4") (pinfunction "A3_4") (pintype "input"))
    )
    (net (code "200") (name "dG_enable") (class "Default")
      (node (ref "DG_R1") (pin "8") (pinfunction "8_8") (pintype "unspecified"))
      (node (ref "H7") (pin "5") (pinfunction "3_5") (pintype "unspecified"))
    )
    (net (code "201") (name "dG_step") (class "Default")
      (node (ref "DG_R1") (pin "2") (pinfunction "2_2") (pintype "unspecified"))
      (node (ref "H6") (pin "10") (pinfunction "8_10") (pintype "unspecified"))
    )
    (net (code "202") (name "dT_PH_VPPH") (class "Default")
      (node (ref "DT_PH_M2") (pin "2") (pinfunction "D_2") (pintype "unspecified"))
      (node (ref "DT_PRINTHEAD1") (pin "3") (pinfunction "VPPH_3") (pintype "unspecified"))
    )
    (net (code "203") (name "dT_PH_VPPL") (class "Default")
      (node (ref "DT_PH_M1") (pin "2") (pinfunction "D_2") (pintype "unspecified"))
      (node (ref "DT_PRINTHEAD1") (pin "4") (pinfunction "VPPL_4") (pintype "unspecified"))
    )
    (net (code "204") (name "dT_PH_fault") (class "Default")
      (node (ref "DT_PRINTHEAD1") (pin "6") (pinfunction "FAULT_6") (pintype "unspecified"))
      (node (ref "U5") (pin "8") (pinfunction "34_8") (pintype "unspecified"))
    )
    (net (code "205") (name "dT_PH_fire") (class "Default")
      (node (ref "DT_PRINTHEAD1") (pin "16") (pinfunction "FIRE_16") (pintype "unspecified"))
      (node (ref "U7") (pin "11") (pinfunction "35_11") (pintype "unspecified"))
    )
    (net (code "206") (name "dT_PH_nSS1") (class "Default")
      (node (ref "DT_PRINTHEAD1") (pin "12") (pinfunction "nSS1_12") (pintype "unspecified"))
      (node (ref "U5") (pin "7") (pinfunction "32_7") (pintype "unspecified"))
    )
    (net (code "207") (name "dT_PH_nSS2") (class "Default")
      (node (ref "DT_PRINTHEAD1") (pin "1") (pinfunction "nSS2_1") (pintype "unspecified"))
      (node (ref "U7") (pin "12") (pinfunction "33_12") (pintype "unspecified"))
    )
    (net (code "208") (name "dT_PH_ready") (class "Default")
      (node (ref "DT_PRINTHEAD1") (pin "14") (pinfunction "READY_14") (pintype "unspecified"))
      (node (ref "U5") (pin "9") (pinfunction "36_9") (pintype "unspecified"))
    )
    (net (code "209") (name "dT_S") (class "Default")
      (node (ref "DT_S_R1") (pin "2") (pinfunction "2_2") (pintype "unspecified"))
      (node (ref "DT_S_R2") (pin "1") (pinfunction "1_1") (pintype "unspecified"))
      (node (ref "H9") (pin "3") (pinfunction "A2_3") (pintype "input"))
    )
    (net (code "210") (name "dT_enable") (class "Default")
      (node (ref "DT_R1") (pin "8") (pinfunction "8_8") (pintype "unspecified"))
      (node (ref "H7") (pin "6") (pinfunction "2_6") (pintype "unspecified"))
    )
    (net (code "211") (name "dT_step") (class "Default")
      (node (ref "DT_R1") (pin "2") (pinfunction "2_2") (pintype "unspecified"))
      (node (ref "H7") (pin "1") (pinfunction "7_1") (pintype "unspecified"))
    )
    (net (code "212") (name "ink_direction") (class "Default")
      (node (ref "ACT_R1") (pin "1") (pinfunction "1_1") (pintype "unspecified"))
      (node (ref "DA_R1") (pin "1") (pinfunction "1_1") (pintype "unspecified"))
      (node (ref "DC_R1") (pin "1") (pinfunction "1_1") (pintype "unspecified"))
      (node (ref "DG_R1") (pin "1") (pinfunction "1_1") (pintype "unspecified"))
      (node (ref "DT_R1") (pin "1") (pinfunction "1_1") (pintype "unspecified"))
      (node (ref "H6") (pin "8") (pinfunction "10_8") (pintype "unspecified"))
    )
    (net (code "213") (name "limit_L_S") (class "Default")
      (node (ref "MEGA-A1") (pin "1") (pinfunction "A0_1") (pintype "unspecified"))
    )
    (net (code "214") (name "limit_R_S") (class "Default")
      (node (ref "MEGA-A1") (pin "2") (pinfunction "A1_2") (pintype "unspecified"))
    )
    (net (code "215") (name "linear_E") (class "Default")
      (node (ref "MEGA-SCL2") (pin "7") (pinfunction "11_7") (pintype "unspecified"))
    )
    (net (code "216") (name "linear_RX") (class "Default")
      (node (ref "MEGA-D2") (pin "4") (pinfunction "17_4") (pintype "unspecified"))
    )
    (net (code "217") (name "linear_TX") (class "Default")
      (node (ref "MEGA-D2") (pin "3") (pinfunction "16_3") (pintype "unspecified"))
    )
    (net (code "218") (name "linear_direction") (class "Default")
      (node (ref "LINEAR_R1") (pin "1") (pinfunction "1_1") (pintype "unspecified"))
    )
    (net (code "219") (name "linear_enable") (class "Default")
      (node (ref "LINEAR_R1") (pin "8") (pinfunction "8_8") (pintype "unspecified"))
    )
    (net (code "220") (name "linear_pulse") (class "Default")
      (node (ref "MEGA-D1") (pin "3") (pinfunction "5_3") (pintype "unspecified"))
    )
    (net (code "221") (name "linear_step") (class "Default")
      (node (ref "LINEAR_R1") (pin "2") (pinfunction "2_2") (pintype "unspecified"))
    )
    (net (code "222") (name "mega_D52") (class "Default")
      (node (ref "ACT_PH_T1") (pin "2") (pinfunction "B_2") (pintype "unspecified"))
      (node (ref "ACT_PH_T2") (pin "2") (pinfunction "B_2") (pintype "unspecified"))
      (node (ref "DA_PH_T1") (pin "2") (pinfunction "B_2") (pintype "unspecified"))
      (node (ref "DA_PH_T2") (pin "2") (pinfunction "B_2") (pintype "unspecified"))
      (node (ref "DC_PH_T1") (pin "2") (pinfunction "B_2") (pintype "unspecified"))
      (node (ref "DC_PH_T2") (pin "2") (pinfunction "B_2") (pintype "unspecified"))
      (node (ref "DG_PH_T1") (pin "2") (pinfunction "B_2") (pintype "unspecified"))
      (node (ref "DG_PH_T2") (pin "2") (pinfunction "B_2") (pintype "unspecified"))
      (node (ref "DT_PH_T1") (pin "2") (pinfunction "B_2") (pintype "unspecified"))
      (node (ref "DT_PH_T2") (pin "2") (pinfunction "B_2") (pintype "unspecified"))
      (node (ref "U5") (pin "17") (pinfunction "52_17") (pintype "unspecified"))
    )
    (net (code "223") (name "unconnected-(H6-12-Pad6)") (class "Default")
      (node (ref "H6") (pin "6") (pinfunction "12_6") (pintype "unspecified"))
    )
    (net (code "224") (name "unconnected-(H6-13-Pad5)") (class "Default")
      (node (ref "H6") (pin "5") (pinfunction "13_5") (pintype "unspecified"))
    )
    (net (code "225") (name "unconnected-(H6-AREF-Pad3)") (class "Default")
      (node (ref "H6") (pin "3") (pinfunction "AREF_3") (pintype "unspecified"))
    )
    (net (code "226") (name "unconnected-(H6-SCL-Pad1)") (class "Default")
      (node (ref "H6") (pin "1") (pinfunction "SCL_1") (pintype "unspecified"))
    )
    (net (code "227") (name "unconnected-(H6-SDA-Pad2)") (class "Default")
      (node (ref "H6") (pin "2") (pinfunction "SDA_2") (pintype "unspecified"))
    )
    (net (code "228") (name "unconnected-(H8-3.3V-Pad4)") (class "Default")
      (node (ref "H8") (pin "4") (pinfunction "3.3V_4") (pintype "unspecified"))
    )
    (net (code "229") (name "unconnected-(H8-IOREF-Pad2)") (class "Default")
      (node (ref "H8") (pin "2") (pinfunction "IOREF_2") (pintype "unspecified"))
    )
    (net (code "230") (name "unconnected-(H8-Pad1)") (class "Default")
      (node (ref "H8") (pin "1") (pintype "unspecified"))
    )
    (net (code "231") (name "unconnected-(MEGA-A1-A2-Pad3)") (class "Default")
      (node (ref "MEGA-A1") (pin "3") (pinfunction "A2_3") (pintype "unspecified"))
    )
    (net (code "232") (name "unconnected-(MEGA-A1-A3-Pad4)") (class "Default")
      (node (ref "MEGA-A1") (pin "4") (pinfunction "A3_4") (pintype "unspecified"))
    )
    (net (code "233") (name "unconnected-(MEGA-A1-A4-Pad5)") (class "Default")
      (node (ref "MEGA-A1") (pin "5") (pinfunction "A4_5") (pintype "unspecified"))
    )
    (net (code "234") (name "unconnected-(MEGA-A1-A5-Pad6)") (class "Default")
      (node (ref "MEGA-A1") (pin "6") (pinfunction "A5_6") (pintype "unspecified"))
    )
    (net (code "235") (name "unconnected-(MEGA-A1-A6-Pad7)") (class "Default")
      (node (ref "MEGA-A1") (pin "7") (pinfunction "A6_7") (pintype "unspecified"))
    )
    (net (code "236") (name "unconnected-(MEGA-A1-A7-Pad8)") (class "Default")
      (node (ref "MEGA-A1") (pin "8") (pinfunction "A7_8") (pintype "unspecified"))
    )
    (net (code "237") (name "unconnected-(MEGA-A2-A8-Pad1)") (class "Default")
      (node (ref "MEGA-A2") (pin "1") (pinfunction "A8_1") (pintype "unspecified"))
    )
    (net (code "238") (name "unconnected-(MEGA-A2-A9-Pad2)") (class "Default")
      (node (ref "MEGA-A2") (pin "2") (pinfunction "A9_2") (pintype "unspecified"))
    )
    (net (code "239") (name "unconnected-(MEGA-A2-A10-Pad3)") (class "Default")
      (node (ref "MEGA-A2") (pin "3") (pinfunction "A10_3") (pintype "unspecified"))
    )
    (net (code "240") (name "unconnected-(MEGA-A2-A11-Pad4)") (class "Default")
      (node (ref "MEGA-A2") (pin "4") (pinfunction "A11_4") (pintype "unspecified"))
    )
    (net (code "241") (name "unconnected-(MEGA-A2-A12-Pad5)") (class "Default")
      (node (ref "MEGA-A2") (pin "5") (pinfunction "A12_5") (pintype "unspecified"))
    )
    (net (code "242") (name "unconnected-(MEGA-A2-A13-Pad6)") (class "Default")
      (node (ref "MEGA-A2") (pin "6") (pinfunction "A13_6") (pintype "unspecified"))
    )
    (net (code "243") (name "unconnected-(MEGA-A2-A14-Pad7)") (class "Default")
      (node (ref "MEGA-A2") (pin "7") (pinfunction "A14_7") (pintype "unspecified"))
    )
    (net (code "244") (name "unconnected-(MEGA-A2-A15-Pad8)") (class "Default")
      (node (ref "MEGA-A2") (pin "8") (pinfunction "A15_8") (pintype "unspecified"))
    )
    (net (code "245") (name "unconnected-(MEGA-IOREF1-3.3V-Pad4)") (class "Default")
      (node (ref "MEGA-IOREF1") (pin "4") (pinfunction "3.3V_4") (pintype "unspecified"))
    )
    (net (code "246") (name "unconnected-(MEGA-IOREF1-IOREF-Pad2)") (class "Default")
      (node (ref "MEGA-IOREF1") (pin "2") (pinfunction "IOREF_2") (pintype "unspecified"))
    )
    (net (code "247") (name "unconnected-(MEGA-IOREF1-Pad1)") (class "Default")
      (node (ref "MEGA-IOREF1") (pin "1") (pintype "unspecified"))
    )
    (net (code "248") (name "unconnected-(MEGA-SCL2-AREF-Pad3)") (class "Default")
      (node (ref "MEGA-SCL2") (pin "3") (pinfunction "AREF_3") (pintype "unspecified"))
    )
    (net (code "249") (name "unconnected-(MEGA-SCL2-SCL-Pad1)") (class "Default")
      (node (ref "MEGA-SCL2") (pin "1") (pinfunction "SCL_1") (pintype "unspecified"))
    )
    (net (code "250") (name "unconnected-(MEGA-SCL2-SDA-Pad2)") (class "Default")
      (node (ref "MEGA-SCL2") (pin "2") (pinfunction "SDA_2") (pintype "unspecified"))
    )
    (net (code "251") (name "unconnected-(SW1-Pad2)") (class "Default")
      (node (ref "SW1") (pin "2") (pinfunction "2_2") (pintype "unspecified"))
    )
    (net (code "252") (name "unconnected-(SW1-Pad4)") (class "Default")
      (node (ref "SW1") (pin "4") (pinfunction "4_4") (pintype "unspecified"))
    )
    (net (code "253") (name "unconnected-(SW3-Pad1)") (class "Default")
      (node (ref "SW3") (pin "1") (pinfunction "1_1") (pintype "unspecified"))
    )
    (net (code "254") (name "unconnected-(SW3-Pad3)") (class "Default")
      (node (ref "SW3") (pin "3") (pinfunction "3_3") (pintype "unspecified"))
    )
    (net (code "255") (name "unconnected-(U7-53-Pad2)") (class "Default")
      (node (ref "U7") (pin "2") (pinfunction "53_2") (pintype "unspecified"))
    )
    (net (code "256") (name "unconnected-(U7-none-Pad18)") (class "Default")
      (node (ref "U7") (pin "18") (pinfunction "none_18") (pintype "unspecified"))
    )
    (net (code "257") (name "valve") (class "Default")
      (node (ref "MEGA-SCL2") (pin "5") (pinfunction "13_5") (pintype "unspecified"))
      (node (ref "R6") (pin "2") (pinfunction "2_2") (pintype "unspecified"))
    )
    (net (code "258") (name "wash_E") (class "Default")
      (node (ref "MEGA-SCL2") (pin "9") (pinfunction "9_9") (pintype "unspecified"))
    )
    (net (code "259") (name "wash_enable") (class "Default")
      (node (ref "WASH_R1") (pin "8") (pinfunction "8_8") (pintype "unspecified"))
    )
    (net (code "260") (name "wash_pulse") (class "Default")
      (node (ref "MEGA-D1") (pin "5") (pinfunction "3_5") (pintype "unspecified"))
    )
    (net (code "261") (name "wash_step") (class "Default")
      (node (ref "WASH_R1") (pin "2") (pinfunction "2_2") (pintype "unspecified"))
    )
    (net (code "262") (name "waste_E") (class "Default")
      (node (ref "MEGA-SCL2") (pin "6") (pinfunction "12_6") (pintype "unspecified"))
    )
    (net (code "263") (name "waste_RX") (class "Default")
      (node (ref "MEGA-D2") (pin "2") (pinfunction "15_2") (pintype "unspecified"))
    )
    (net (code "264") (name "waste_TX") (class "Default")
      (node (ref "MEGA-D2") (pin "1") (pinfunction "14_1") (pintype "unspecified"))
    )
    (net (code "265") (name "waste_enable") (class "Default")
      (node (ref "WASTE1_R") (pin "8") (pinfunction "8_8") (pintype "unspecified"))
      (node (ref "WASTE2_R") (pin "8") (pinfunction "8_8") (pintype "unspecified"))
    )
    (net (code "266") (name "waste_pulse") (class "Default")
      (node (ref "MEGA-D1") (pin "2") (pinfunction "6_2") (pintype "unspecified"))
    )
    (net (code "267") (name "waste_step") (class "Default")
      (node (ref "WASTE1_R") (pin "2") (pinfunction "2_2") (pintype "unspecified"))
      (node (ref "WASTE2_R") (pin "2") (pinfunction "2_2") (pintype "unspecified"))
    )
  )
)
